# demo_dermis_main_testboard_ncd2400.net
KiCad netlist of a schematic drawn in Altium Designer
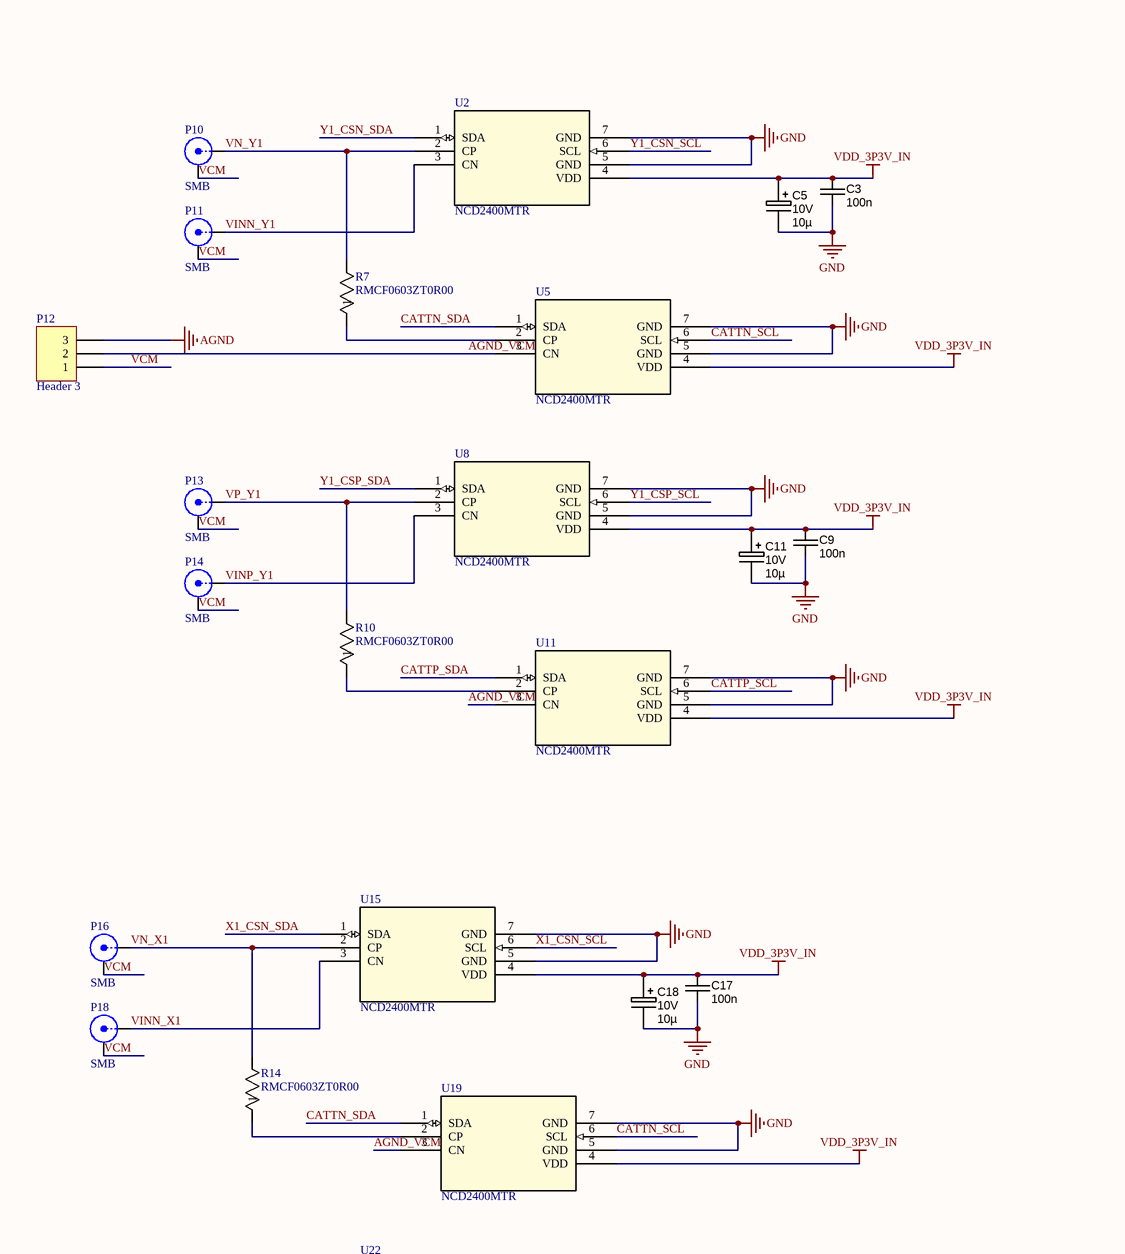
[diagram p0: demo_dermis_main_testboard_ncd2400.SchDoc, top left]
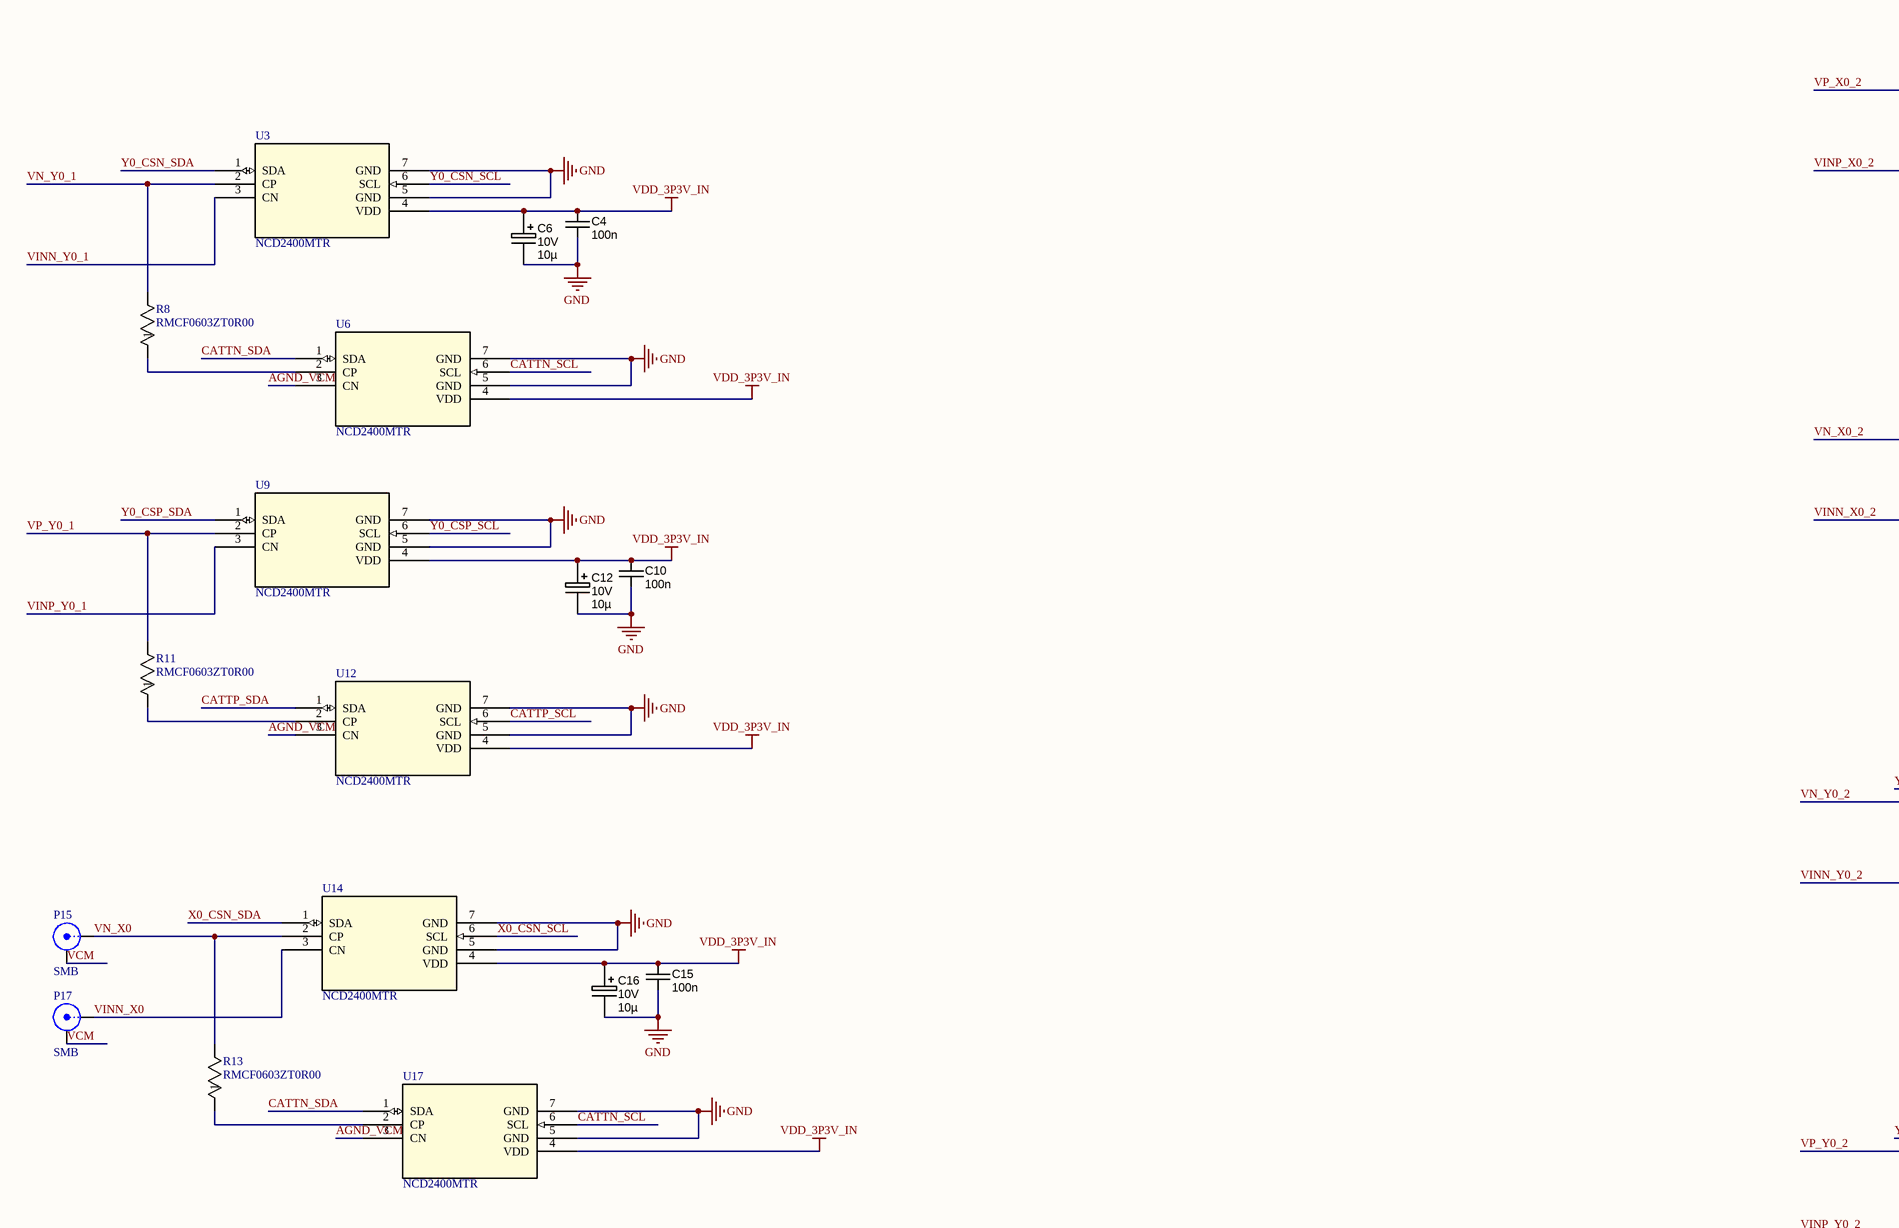
[diagram p1: demo_dermis_main_testboard_ncd2400.SchDoc, top middle]
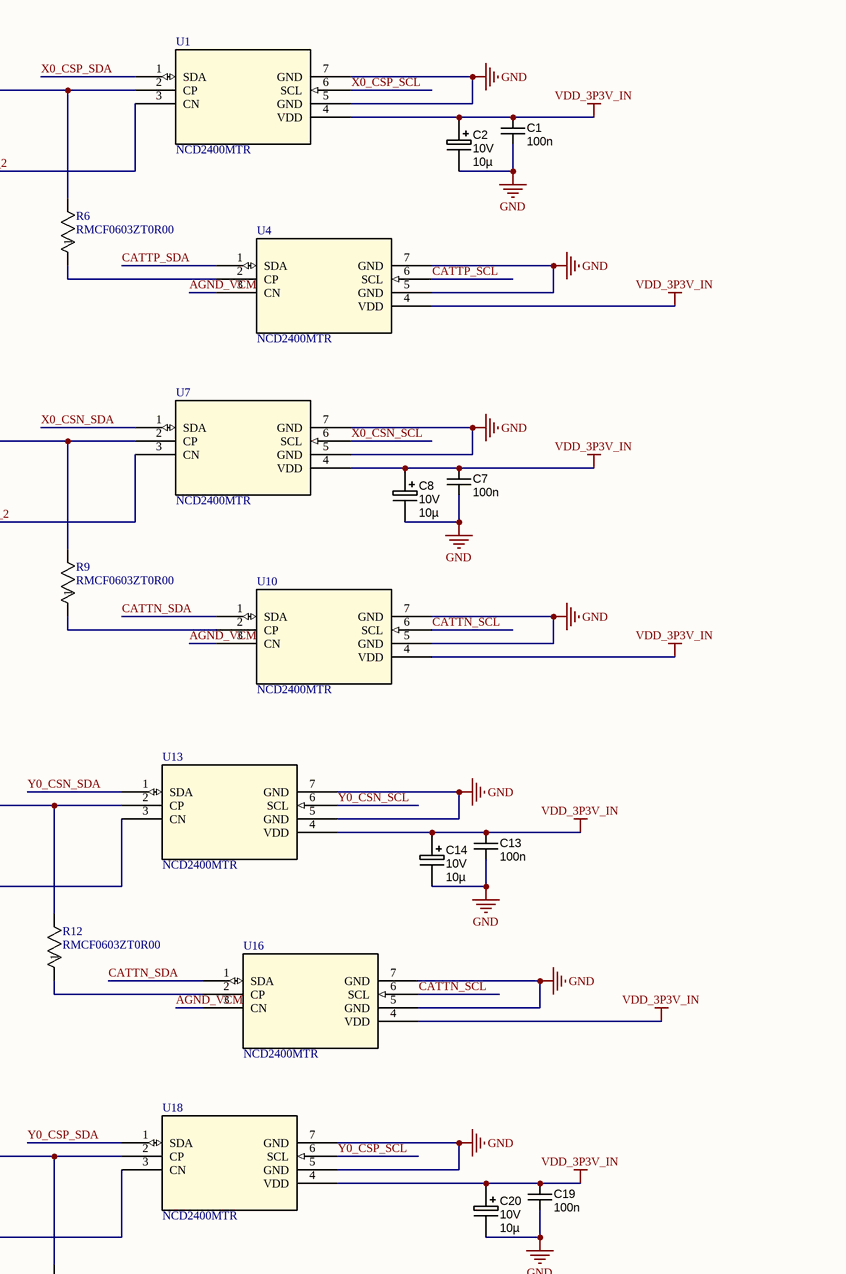
[diagram p2: demo_dermis_main_testboard_ncd2400.SchDoc, top right]
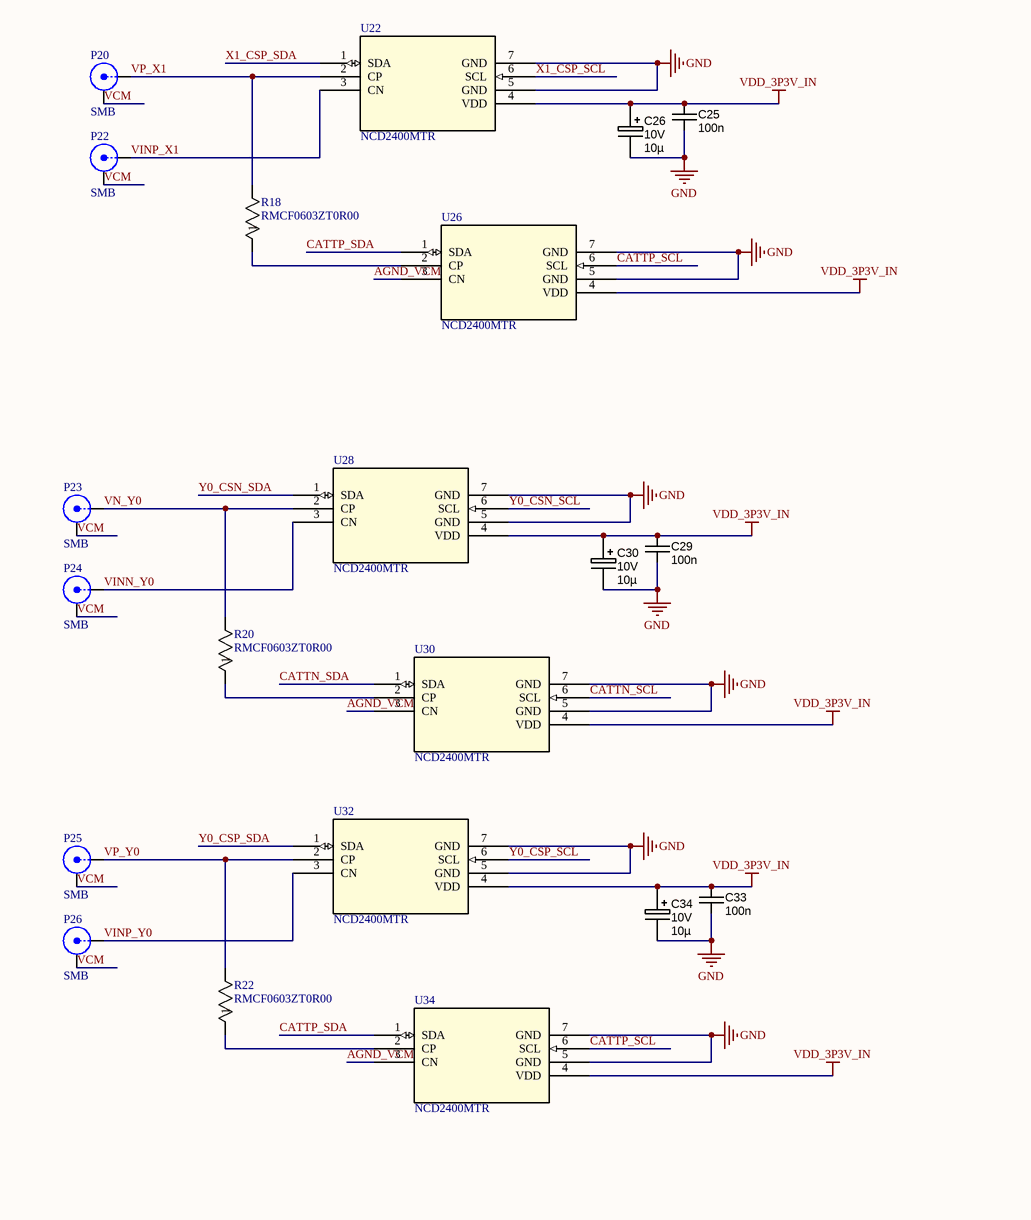
[diagram p3: demo_dermis_main_testboard_ncd2400.SchDoc, bottom left]
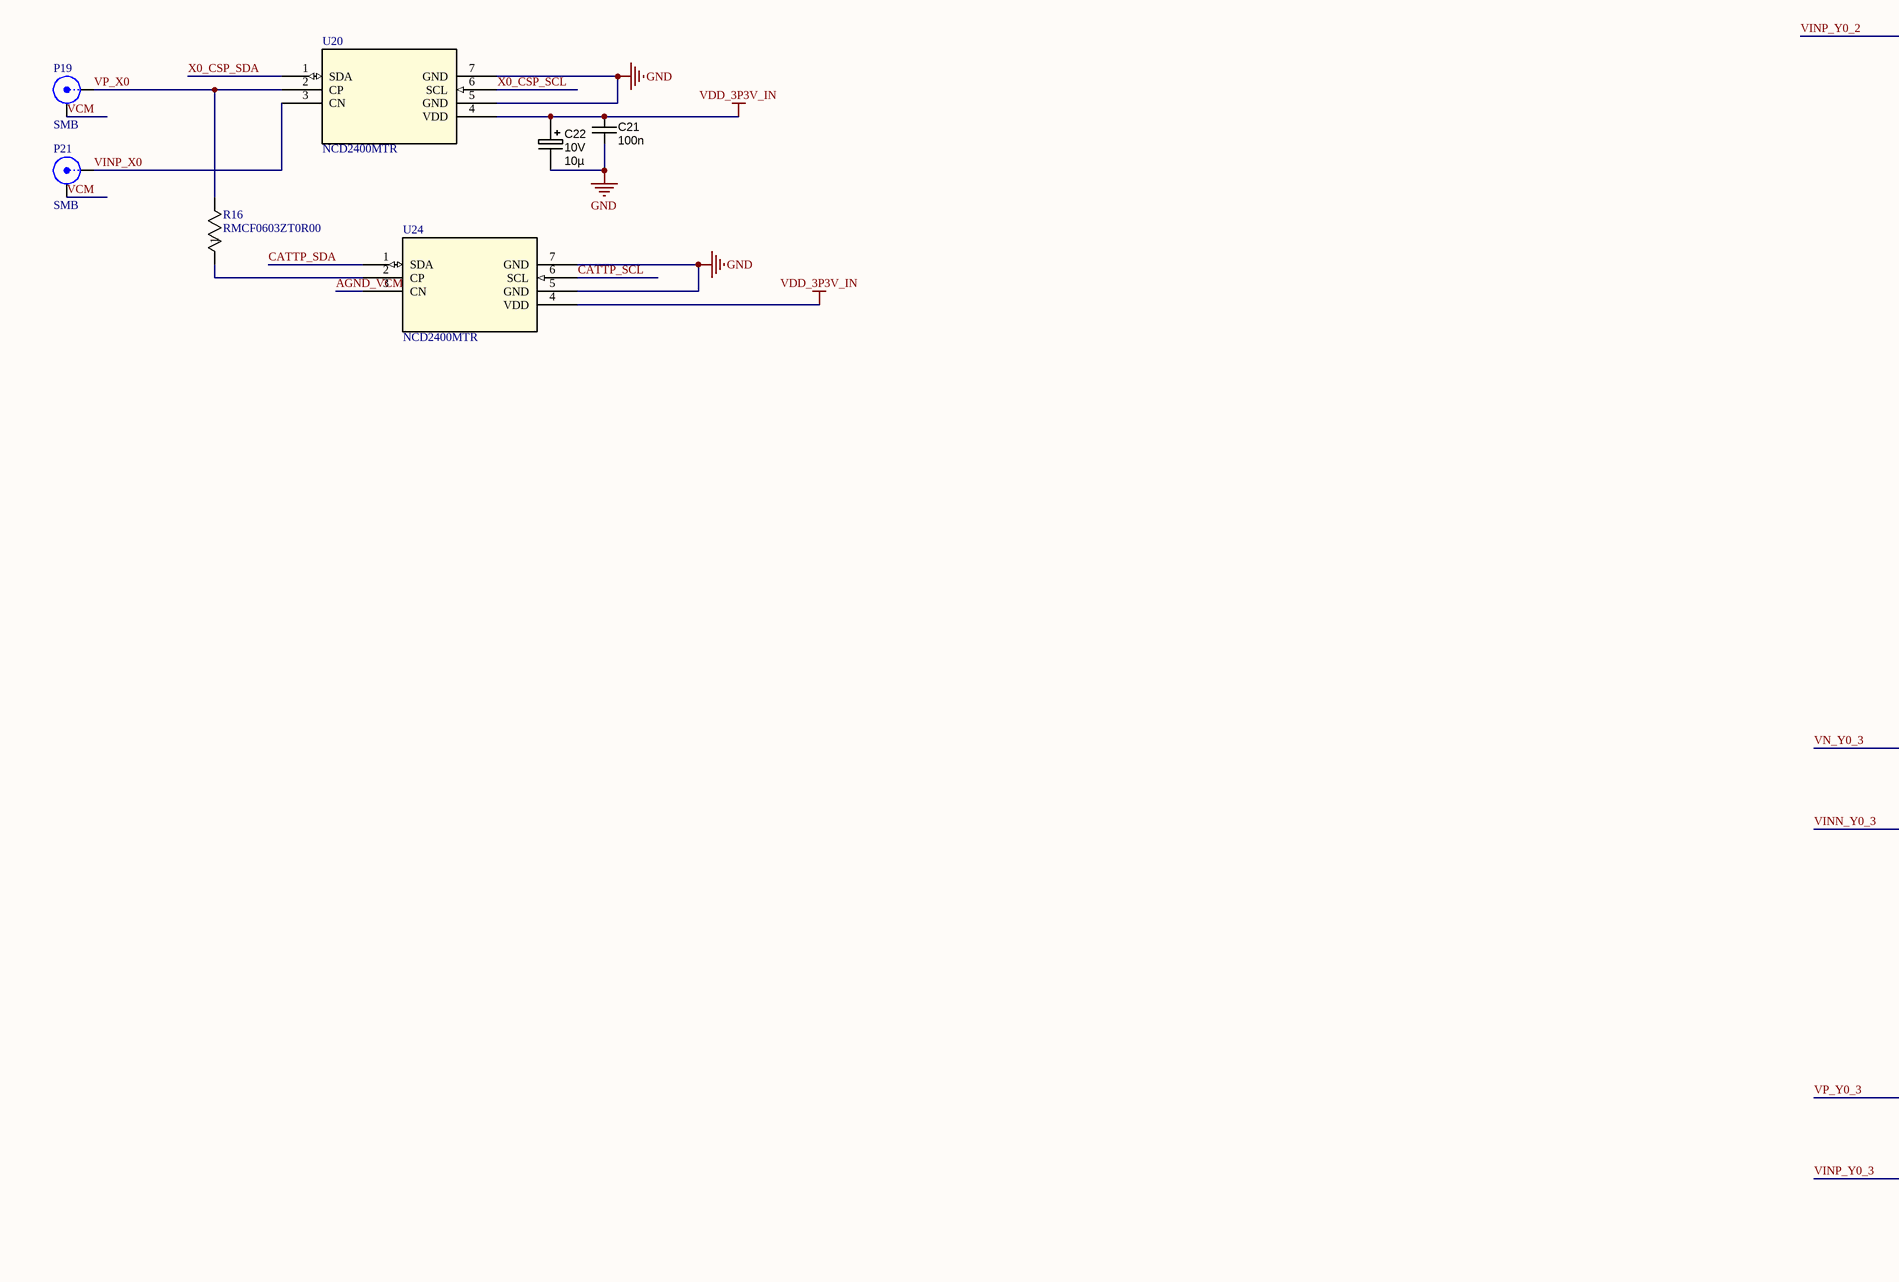
[diagram p4: demo_dermis_main_testboard_ncd2400.SchDoc, bottom middle]
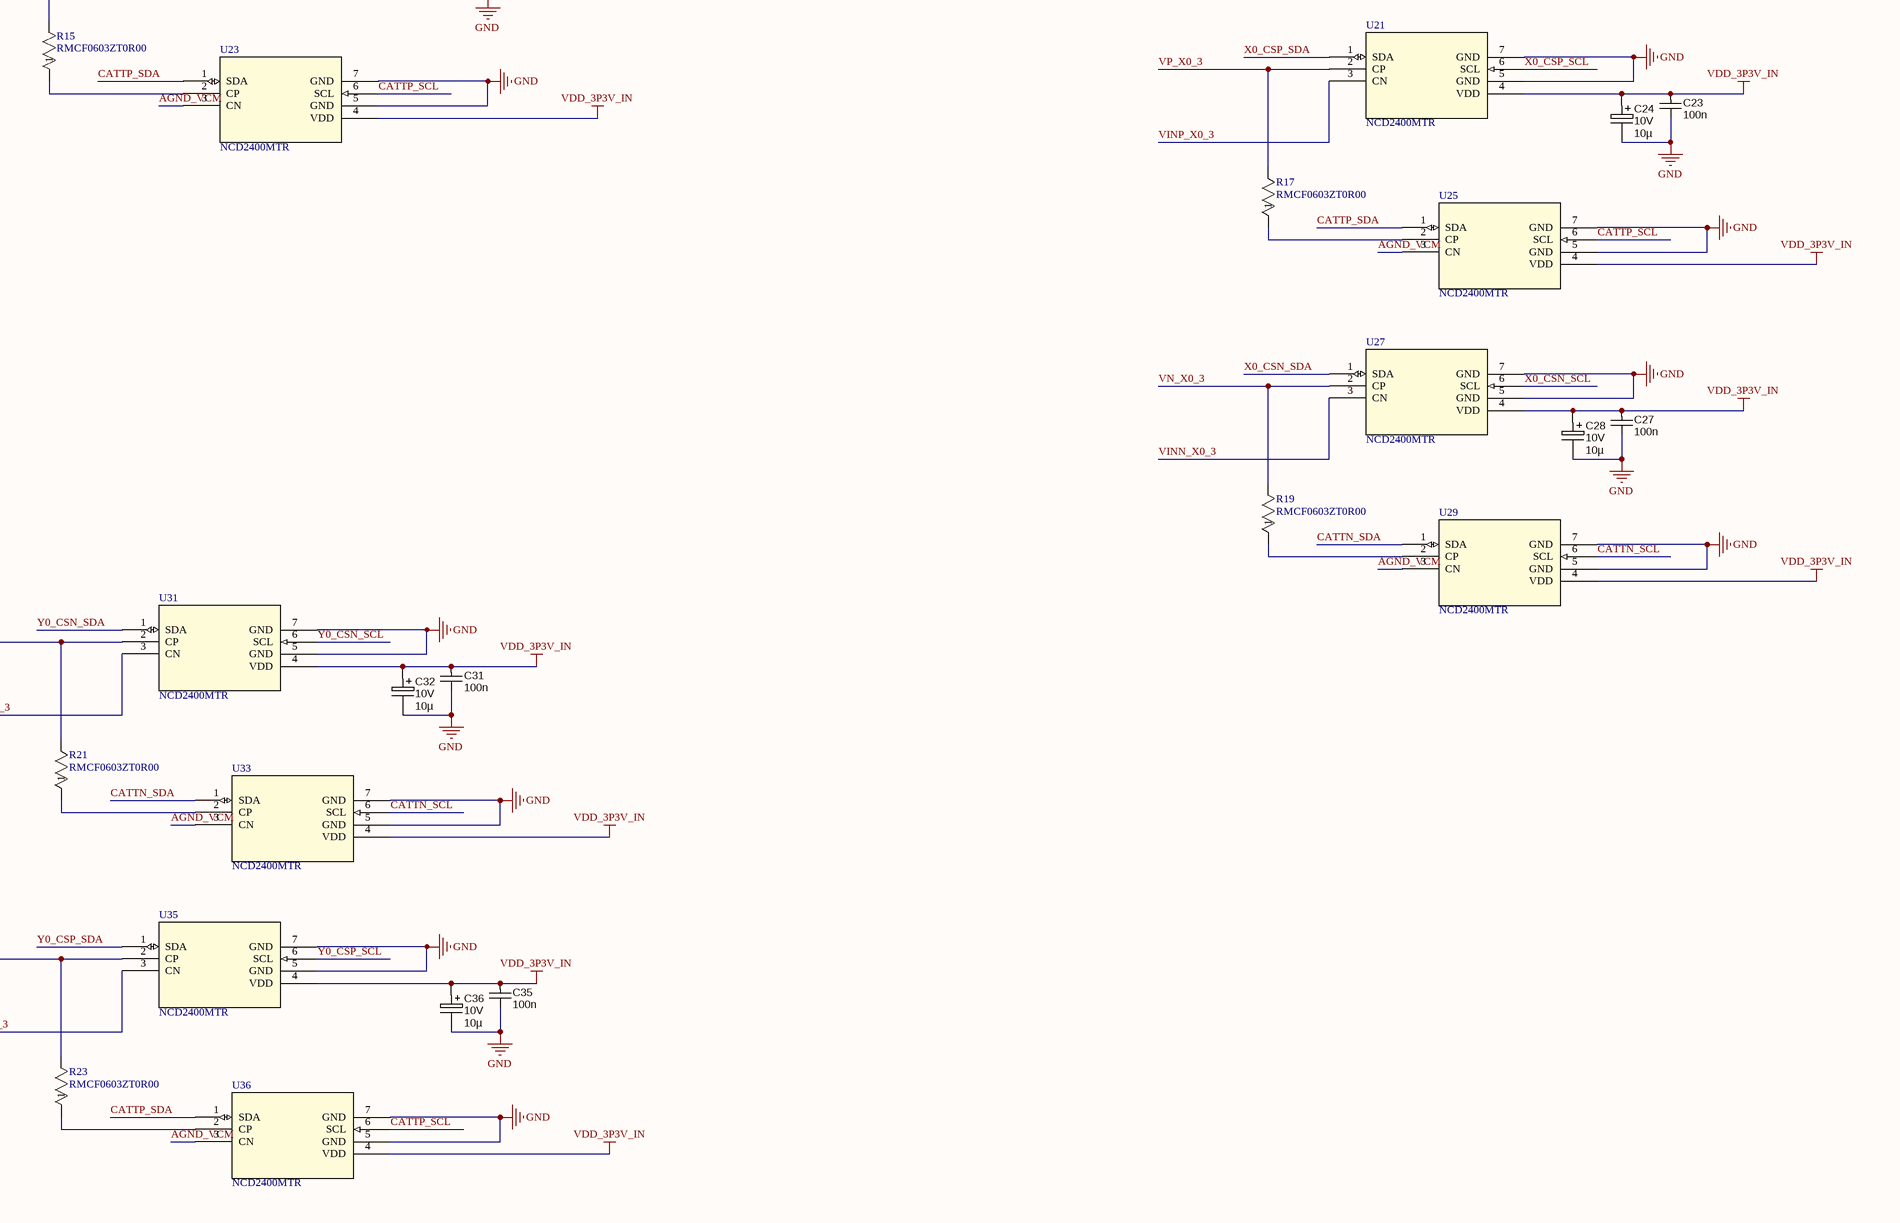
[diagram p5: demo_dermis_main_testboard_ncd2400.SchDoc, bottom right]

(export (version "E")
  (design (tool "Eeschema 10.0.6"))
  (components
    (comp (ref "C1")
      (value "100n")
      (footprint "CAPC1608N")
      (description "Capacitor SMD Cer 100nF 10% 50V X7R 0603")
      (fields (field (name "TOLERANCE") "±10%") (field (name "Comment") "approved sub OK"))
      (libsource (lib "PBL - Capacitors") (part "CAPC_100n_0603"))
    )
    (comp (ref "C2")
      (value "10µ")
      (footprint "CAPMP2012X150USR")
      (description "Capacitor SMD Tantalum 10uF 20% 10V 0805")
      (fields (field (name "TOLERANCE") "±20%") (field (name "RATINGS") "10V"))
      (libsource (lib "PBL - Capacitors") (part "CAPT_10u_0805_10V"))
    )
    (comp (ref "C3")
      (value "100n")
      (footprint "CAPC1608N")
      (description "Capacitor SMD Cer 100nF 10% 50V X7R 0603")
      (fields (field (name "TOLERANCE") "±10%") (field (name "Comment") "approved sub OK"))
      (libsource (lib "PBL - Capacitors") (part "CAPC_100n_0603"))
    )
    (comp (ref "C4")
      (value "100n")
      (footprint "CAPC1608N")
      (description "Capacitor SMD Cer 100nF 10% 50V X7R 0603")
      (fields (field (name "TOLERANCE") "±10%") (field (name "Comment") "approved sub OK"))
      (libsource (lib "PBL - Capacitors") (part "CAPC_100n_0603"))
    )
    (comp (ref "C5")
      (value "10µ")
      (footprint "CAPMP2012X150USR")
      (description "Capacitor SMD Tantalum 10uF 20% 10V 0805")
      (fields (field (name "TOLERANCE") "±20%") (field (name "RATINGS") "10V"))
      (libsource (lib "PBL - Capacitors") (part "CAPT_10u_0805_10V"))
    )
    (comp (ref "C6")
      (value "10µ")
      (footprint "CAPMP2012X150USR")
      (description "Capacitor SMD Tantalum 10uF 20% 10V 0805")
      (fields (field (name "TOLERANCE") "±20%") (field (name "RATINGS") "10V"))
      (libsource (lib "PBL - Capacitors") (part "CAPT_10u_0805_10V"))
    )
    (comp (ref "C7")
      (value "100n")
      (footprint "CAPC1608N")
      (description "Capacitor SMD Cer 100nF 10% 50V X7R 0603")
      (fields (field (name "TOLERANCE") "±10%") (field (name "Comment") "approved sub OK"))
      (libsource (lib "PBL - Capacitors") (part "CAPC_100n_0603"))
    )
    (comp (ref "C8")
      (value "10µ")
      (footprint "CAPMP2012X150USR")
      (description "Capacitor SMD Tantalum 10uF 20% 10V 0805")
      (fields (field (name "TOLERANCE") "±20%") (field (name "RATINGS") "10V"))
      (libsource (lib "PBL - Capacitors") (part "CAPT_10u_0805_10V"))
    )
    (comp (ref "C9")
      (value "100n")
      (footprint "CAPC1608N")
      (description "Capacitor SMD Cer 100nF 10% 50V X7R 0603")
      (fields (field (name "TOLERANCE") "±10%") (field (name "Comment") "approved sub OK"))
      (libsource (lib "PBL - Capacitors") (part "CAPC_100n_0603"))
    )
    (comp (ref "C10")
      (value "100n")
      (footprint "CAPC1608N")
      (description "Capacitor SMD Cer 100nF 10% 50V X7R 0603")
      (fields (field (name "TOLERANCE") "±10%") (field (name "Comment") "approved sub OK"))
      (libsource (lib "PBL - Capacitors") (part "CAPC_100n_0603"))
    )
    (comp (ref "C11")
      (value "10µ")
      (footprint "CAPMP2012X150USR")
      (description "Capacitor SMD Tantalum 10uF 20% 10V 0805")
      (fields (field (name "TOLERANCE") "±20%") (field (name "RATINGS") "10V"))
      (libsource (lib "PBL - Capacitors") (part "CAPT_10u_0805_10V"))
    )
    (comp (ref "C12")
      (value "10µ")
      (footprint "CAPMP2012X150USR")
      (description "Capacitor SMD Tantalum 10uF 20% 10V 0805")
      (fields (field (name "TOLERANCE") "±20%") (field (name "RATINGS") "10V"))
      (libsource (lib "PBL - Capacitors") (part "CAPT_10u_0805_10V"))
    )
    (comp (ref "C13")
      (value "100n")
      (footprint "CAPC1608N")
      (description "Capacitor SMD Cer 100nF 10% 50V X7R 0603")
      (fields (field (name "TOLERANCE") "±10%") (field (name "Comment") "approved sub OK"))
      (libsource (lib "PBL - Capacitors") (part "CAPC_100n_0603"))
    )
    (comp (ref "C14")
      (value "10µ")
      (footprint "CAPMP2012X150USR")
      (description "Capacitor SMD Tantalum 10uF 20% 10V 0805")
      (fields (field (name "TOLERANCE") "±20%") (field (name "RATINGS") "10V"))
      (libsource (lib "PBL - Capacitors") (part "CAPT_10u_0805_10V"))
    )
    (comp (ref "C15")
      (value "100n")
      (footprint "CAPC1608N")
      (description "Capacitor SMD Cer 100nF 10% 50V X7R 0603")
      (fields (field (name "TOLERANCE") "±10%") (field (name "Comment") "approved sub OK"))
      (libsource (lib "PBL - Capacitors") (part "CAPC_100n_0603"))
    )
    (comp (ref "C16")
      (value "10µ")
      (footprint "CAPMP2012X150USR")
      (description "Capacitor SMD Tantalum 10uF 20% 10V 0805")
      (fields (field (name "TOLERANCE") "±20%") (field (name "RATINGS") "10V"))
      (libsource (lib "PBL - Capacitors") (part "CAPT_10u_0805_10V"))
    )
    (comp (ref "C17")
      (value "100n")
      (footprint "CAPC1608N")
      (description "Capacitor SMD Cer 100nF 10% 50V X7R 0603")
      (fields (field (name "TOLERANCE") "±10%") (field (name "Comment") "approved sub OK"))
      (libsource (lib "PBL - Capacitors") (part "CAPC_100n_0603"))
    )
    (comp (ref "C18")
      (value "10µ")
      (footprint "CAPMP2012X150USR")
      (description "Capacitor SMD Tantalum 10uF 20% 10V 0805")
      (fields (field (name "TOLERANCE") "±20%") (field (name "RATINGS") "10V"))
      (libsource (lib "PBL - Capacitors") (part "CAPT_10u_0805_10V"))
    )
    (comp (ref "C19")
      (value "100n")
      (footprint "CAPC1608N")
      (description "Capacitor SMD Cer 100nF 10% 50V X7R 0603")
      (fields (field (name "TOLERANCE") "±10%") (field (name "Comment") "approved sub OK"))
      (libsource (lib "PBL - Capacitors") (part "CAPC_100n_0603"))
    )
    (comp (ref "C20")
      (value "10µ")
      (footprint "CAPMP2012X150USR")
      (description "Capacitor SMD Tantalum 10uF 20% 10V 0805")
      (fields (field (name "TOLERANCE") "±20%") (field (name "RATINGS") "10V"))
      (libsource (lib "PBL - Capacitors") (part "CAPT_10u_0805_10V"))
    )
    (comp (ref "C21")
      (value "100n")
      (footprint "CAPC1608N")
      (description "Capacitor SMD Cer 100nF 10% 50V X7R 0603")
      (fields (field (name "TOLERANCE") "±10%") (field (name "Comment") "approved sub OK"))
      (libsource (lib "PBL - Capacitors") (part "CAPC_100n_0603"))
    )
    (comp (ref "C22")
      (value "10µ")
      (footprint "CAPMP2012X150USR")
      (description "Capacitor SMD Tantalum 10uF 20% 10V 0805")
      (fields (field (name "TOLERANCE") "±20%") (field (name "RATINGS") "10V"))
      (libsource (lib "PBL - Capacitors") (part "CAPT_10u_0805_10V"))
    )
    (comp (ref "C23")
      (value "100n")
      (footprint "CAPC1608N")
      (description "Capacitor SMD Cer 100nF 10% 50V X7R 0603")
      (fields (field (name "TOLERANCE") "±10%") (field (name "Comment") "approved sub OK"))
      (libsource (lib "PBL - Capacitors") (part "CAPC_100n_0603"))
    )
    (comp (ref "C24")
      (value "10µ")
      (footprint "CAPMP2012X150USR")
      (description "Capacitor SMD Tantalum 10uF 20% 10V 0805")
      (fields (field (name "TOLERANCE") "±20%") (field (name "RATINGS") "10V"))
      (libsource (lib "PBL - Capacitors") (part "CAPT_10u_0805_10V"))
    )
    (comp (ref "C25")
      (value "100n")
      (footprint "CAPC1608N")
      (description "Capacitor SMD Cer 100nF 10% 50V X7R 0603")
      (fields (field (name "TOLERANCE") "±10%") (field (name "Comment") "approved sub OK"))
      (libsource (lib "PBL - Capacitors") (part "CAPC_100n_0603"))
    )
    (comp (ref "C26")
      (value "10µ")
      (footprint "CAPMP2012X150USR")
      (description "Capacitor SMD Tantalum 10uF 20% 10V 0805")
      (fields (field (name "TOLERANCE") "±20%") (field (name "RATINGS") "10V"))
      (libsource (lib "PBL - Capacitors") (part "CAPT_10u_0805_10V"))
    )
    (comp (ref "C27")
      (value "100n")
      (footprint "CAPC1608N")
      (description "Capacitor SMD Cer 100nF 10% 50V X7R 0603")
      (fields (field (name "TOLERANCE") "±10%") (field (name "Comment") "approved sub OK"))
      (libsource (lib "PBL - Capacitors") (part "CAPC_100n_0603"))
    )
    (comp (ref "C28")
      (value "10µ")
      (footprint "CAPMP2012X150USR")
      (description "Capacitor SMD Tantalum 10uF 20% 10V 0805")
      (fields (field (name "TOLERANCE") "±20%") (field (name "RATINGS") "10V"))
      (libsource (lib "PBL - Capacitors") (part "CAPT_10u_0805_10V"))
    )
    (comp (ref "C29")
      (value "100n")
      (footprint "CAPC1608N")
      (description "Capacitor SMD Cer 100nF 10% 50V X7R 0603")
      (fields (field (name "TOLERANCE") "±10%") (field (name "Comment") "approved sub OK"))
      (libsource (lib "PBL - Capacitors") (part "CAPC_100n_0603"))
    )
    (comp (ref "C30")
      (value "10µ")
      (footprint "CAPMP2012X150USR")
      (description "Capacitor SMD Tantalum 10uF 20% 10V 0805")
      (fields (field (name "TOLERANCE") "±20%") (field (name "RATINGS") "10V"))
      (libsource (lib "PBL - Capacitors") (part "CAPT_10u_0805_10V"))
    )
    (comp (ref "C31")
      (value "100n")
      (footprint "CAPC1608N")
      (description "Capacitor SMD Cer 100nF 10% 50V X7R 0603")
      (fields (field (name "TOLERANCE") "±10%") (field (name "Comment") "approved sub OK"))
      (libsource (lib "PBL - Capacitors") (part "CAPC_100n_0603"))
    )
    (comp (ref "C32")
      (value "10µ")
      (footprint "CAPMP2012X150USR")
      (description "Capacitor SMD Tantalum 10uF 20% 10V 0805")
      (fields (field (name "TOLERANCE") "±20%") (field (name "RATINGS") "10V"))
      (libsource (lib "PBL - Capacitors") (part "CAPT_10u_0805_10V"))
    )
    (comp (ref "C33")
      (value "100n")
      (footprint "CAPC1608N")
      (description "Capacitor SMD Cer 100nF 10% 50V X7R 0603")
      (fields (field (name "TOLERANCE") "±10%") (field (name "Comment") "approved sub OK"))
      (libsource (lib "PBL - Capacitors") (part "CAPC_100n_0603"))
    )
    (comp (ref "C34")
      (value "10µ")
      (footprint "CAPMP2012X150USR")
      (description "Capacitor SMD Tantalum 10uF 20% 10V 0805")
      (fields (field (name "TOLERANCE") "±20%") (field (name "RATINGS") "10V"))
      (libsource (lib "PBL - Capacitors") (part "CAPT_10u_0805_10V"))
    )
    (comp (ref "C35")
      (value "100n")
      (footprint "CAPC1608N")
      (description "Capacitor SMD Cer 100nF 10% 50V X7R 0603")
      (fields (field (name "TOLERANCE") "±10%") (field (name "Comment") "approved sub OK"))
      (libsource (lib "PBL - Capacitors") (part "CAPC_100n_0603"))
    )
    (comp (ref "C36")
      (value "10µ")
      (footprint "CAPMP2012X150USR")
      (description "Capacitor SMD Tantalum 10uF 20% 10V 0805")
      (fields (field (name "TOLERANCE") "±20%") (field (name "RATINGS") "10V"))
      (libsource (lib "PBL - Capacitors") (part "CAPT_10u_0805_10V"))
    )
    (comp (ref "P10")
      (value "SMB")
      (footprint "SMB_V-RJ45")
      (description "SMB Straight Connector")
      (fields (field (name "PUBLISHER") "Altium Limited"))
      (libsource (lib "Miscellaneous Connectors") (part "SMB"))
    )
    (comp (ref "P11")
      (value "SMB")
      (footprint "SMB_V-RJ45")
      (description "SMB Straight Connector")
      (fields (field (name "PUBLISHER") "Altium Limited"))
      (libsource (lib "Miscellaneous Connectors") (part "SMB"))
    )
    (comp (ref "P12")
      (value "Header 3")
      (footprint "HDR1X3")
      (description "Header, 3-Pin")
      (fields (field (name "PUBLISHER") "Altium Limited"))
      (libsource (lib "Miscellaneous Connectors") (part "Header 3"))
    )
    (comp (ref "P13")
      (value "SMB")
      (footprint "SMB_V-RJ45")
      (description "SMB Straight Connector")
      (fields (field (name "PUBLISHER") "Altium Limited"))
      (libsource (lib "Miscellaneous Connectors") (part "SMB"))
    )
    (comp (ref "P14")
      (value "SMB")
      (footprint "SMB_V-RJ45")
      (description "SMB Straight Connector")
      (fields (field (name "PUBLISHER") "Altium Limited"))
      (libsource (lib "Miscellaneous Connectors") (part "SMB"))
    )
    (comp (ref "P15")
      (value "SMB")
      (footprint "SMB_V-RJ45")
      (description "SMB Straight Connector")
      (fields (field (name "PUBLISHER") "Altium Limited"))
      (libsource (lib "Miscellaneous Connectors") (part "SMB"))
    )
    (comp (ref "P16")
      (value "SMB")
      (footprint "SMB_V-RJ45")
      (description "SMB Straight Connector")
      (fields (field (name "PUBLISHER") "Altium Limited"))
      (libsource (lib "Miscellaneous Connectors") (part "SMB"))
    )
    (comp (ref "P17")
      (value "SMB")
      (footprint "SMB_V-RJ45")
      (description "SMB Straight Connector")
      (fields (field (name "PUBLISHER") "Altium Limited"))
      (libsource (lib "Miscellaneous Connectors") (part "SMB"))
    )
    (comp (ref "P18")
      (value "SMB")
      (footprint "SMB_V-RJ45")
      (description "SMB Straight Connector")
      (fields (field (name "PUBLISHER") "Altium Limited"))
      (libsource (lib "Miscellaneous Connectors") (part "SMB"))
    )
    (comp (ref "P19")
      (value "SMB")
      (footprint "SMB_V-RJ45")
      (description "SMB Straight Connector")
      (fields (field (name "PUBLISHER") "Altium Limited"))
      (libsource (lib "Miscellaneous Connectors") (part "SMB"))
    )
    (comp (ref "P20")
      (value "SMB")
      (footprint "SMB_V-RJ45")
      (description "SMB Straight Connector")
      (fields (field (name "PUBLISHER") "Altium Limited"))
      (libsource (lib "Miscellaneous Connectors") (part "SMB"))
    )
    (comp (ref "P21")
      (value "SMB")
      (footprint "SMB_V-RJ45")
      (description "SMB Straight Connector")
      (fields (field (name "PUBLISHER") "Altium Limited"))
      (libsource (lib "Miscellaneous Connectors") (part "SMB"))
    )
    (comp (ref "P22")
      (value "SMB")
      (footprint "SMB_V-RJ45")
      (description "SMB Straight Connector")
      (fields (field (name "PUBLISHER") "Altium Limited"))
      (libsource (lib "Miscellaneous Connectors") (part "SMB"))
    )
    (comp (ref "P23")
      (value "SMB")
      (footprint "SMB_V-RJ45")
      (description "SMB Straight Connector")
      (fields (field (name "PUBLISHER") "Altium Limited"))
      (libsource (lib "Miscellaneous Connectors") (part "SMB"))
    )
    (comp (ref "P24")
      (value "SMB")
      (footprint "SMB_V-RJ45")
      (description "SMB Straight Connector")
      (fields (field (name "PUBLISHER") "Altium Limited"))
      (libsource (lib "Miscellaneous Connectors") (part "SMB"))
    )
    (comp (ref "P25")
      (value "SMB")
      (footprint "SMB_V-RJ45")
      (description "SMB Straight Connector")
      (fields (field (name "PUBLISHER") "Altium Limited"))
      (libsource (lib "Miscellaneous Connectors") (part "SMB"))
    )
    (comp (ref "P26")
      (value "SMB")
      (footprint "SMB_V-RJ45")
      (description "SMB Straight Connector")
      (fields (field (name "PUBLISHER") "Altium Limited"))
      (libsource (lib "Miscellaneous Connectors") (part "SMB"))
    )
    (comp (ref "R6")
      (value "RMCF0603ZT0R00")
      (footprint "STA_RMCF0603_STP")
      (description "No Description Available")
      (libsource (lib "RMCF0603ZT0R00") (part "RMCF0603ZT0R00"))
    )
    (comp (ref "R7")
      (value "RMCF0603ZT0R00")
      (footprint "STA_RMCF0603_STP")
      (description "No Description Available")
      (libsource (lib "RMCF0603ZT0R00") (part "RMCF0603ZT0R00"))
    )
    (comp (ref "R8")
      (value "RMCF0603ZT0R00")
      (footprint "STA_RMCF0603_STP")
      (description "No Description Available")
      (libsource (lib "RMCF0603ZT0R00") (part "RMCF0603ZT0R00"))
    )
    (comp (ref "R9")
      (value "RMCF0603ZT0R00")
      (footprint "STA_RMCF0603_STP")
      (description "No Description Available")
      (libsource (lib "RMCF0603ZT0R00") (part "RMCF0603ZT0R00"))
    )
    (comp (ref "R10")
      (value "RMCF0603ZT0R00")
      (footprint "STA_RMCF0603_STP")
      (description "No Description Available")
      (libsource (lib "RMCF0603ZT0R00") (part "RMCF0603ZT0R00"))
    )
    (comp (ref "R11")
      (value "RMCF0603ZT0R00")
      (footprint "STA_RMCF0603_STP")
      (description "No Description Available")
      (libsource (lib "RMCF0603ZT0R00") (part "RMCF0603ZT0R00"))
    )
    (comp (ref "R12")
      (value "RMCF0603ZT0R00")
      (footprint "STA_RMCF0603_STP")
      (description "No Description Available")
      (libsource (lib "RMCF0603ZT0R00") (part "RMCF0603ZT0R00"))
    )
    (comp (ref "R13")
      (value "RMCF0603ZT0R00")
      (footprint "STA_RMCF0603_STP")
      (description "No Description Available")
      (libsource (lib "RMCF0603ZT0R00") (part "RMCF0603ZT0R00"))
    )
    (comp (ref "R14")
      (value "RMCF0603ZT0R00")
      (footprint "STA_RMCF0603_STP")
      (description "No Description Available")
      (libsource (lib "RMCF0603ZT0R00") (part "RMCF0603ZT0R00"))
    )
    (comp (ref "R15")
      (value "RMCF0603ZT0R00")
      (footprint "STA_RMCF0603_STP")
      (description "No Description Available")
      (libsource (lib "RMCF0603ZT0R00") (part "RMCF0603ZT0R00"))
    )
    (comp (ref "R16")
      (value "RMCF0603ZT0R00")
      (footprint "STA_RMCF0603_STP")
      (description "No Description Available")
      (libsource (lib "RMCF0603ZT0R00") (part "RMCF0603ZT0R00"))
    )
    (comp (ref "R17")
      (value "RMCF0603ZT0R00")
      (footprint "STA_RMCF0603_STP")
      (description "No Description Available")
      (libsource (lib "RMCF0603ZT0R00") (part "RMCF0603ZT0R00"))
    )
    (comp (ref "R18")
      (value "RMCF0603ZT0R00")
      (footprint "STA_RMCF0603_STP")
      (description "No Description Available")
      (libsource (lib "RMCF0603ZT0R00") (part "RMCF0603ZT0R00"))
    )
    (comp (ref "R19")
      (value "RMCF0603ZT0R00")
      (footprint "STA_RMCF0603_STP")
      (description "No Description Available")
      (libsource (lib "RMCF0603ZT0R00") (part "RMCF0603ZT0R00"))
    )
    (comp (ref "R20")
      (value "RMCF0603ZT0R00")
      (footprint "STA_RMCF0603_STP")
      (description "No Description Available")
      (libsource (lib "RMCF0603ZT0R00") (part "RMCF0603ZT0R00"))
    )
    (comp (ref "R21")
      (value "RMCF0603ZT0R00")
      (footprint "STA_RMCF0603_STP")
      (description "No Description Available")
      (libsource (lib "RMCF0603ZT0R00") (part "RMCF0603ZT0R00"))
    )
    (comp (ref "R22")
      (value "RMCF0603ZT0R00")
      (footprint "STA_RMCF0603_STP")
      (description "No Description Available")
      (libsource (lib "RMCF0603ZT0R00") (part "RMCF0603ZT0R00"))
    )
    (comp (ref "R23")
      (value "RMCF0603ZT0R00")
      (footprint "STA_RMCF0603_STP")
      (description "No Description Available")
      (libsource (lib "RMCF0603ZT0R00") (part "RMCF0603ZT0R00"))
    )
    (comp (ref "U1")
      (value "NCD2400MTR")
      (footprint "DFN-6_IXY")
      (description "No Description Available")
      (libsource (lib "NCD2400MTR") (part "NCD2400MTR"))
    )
    (comp (ref "U2")
      (value "NCD2400MTR")
      (footprint "DFN-6_IXY")
      (description "No Description Available")
      (libsource (lib "NCD2400MTR") (part "NCD2400MTR"))
    )
    (comp (ref "U3")
      (value "NCD2400MTR")
      (footprint "DFN-6_IXY")
      (description "No Description Available")
      (libsource (lib "NCD2400MTR") (part "NCD2400MTR"))
    )
    (comp (ref "U4")
      (value "NCD2400MTR")
      (footprint "DFN-6_IXY")
      (description "No Description Available")
      (libsource (lib "NCD2400MTR") (part "NCD2400MTR"))
    )
    (comp (ref "U5")
      (value "NCD2400MTR")
      (footprint "DFN-6_IXY")
      (description "No Description Available")
      (libsource (lib "NCD2400MTR") (part "NCD2400MTR"))
    )
    (comp (ref "U6")
      (value "NCD2400MTR")
      (footprint "DFN-6_IXY")
      (description "No Description Available")
      (libsource (lib "NCD2400MTR") (part "NCD2400MTR"))
    )
    (comp (ref "U7")
      (value "NCD2400MTR")
      (footprint "DFN-6_IXY")
      (description "No Description Available")
      (libsource (lib "NCD2400MTR") (part "NCD2400MTR"))
    )
    (comp (ref "U8")
      (value "NCD2400MTR")
      (footprint "DFN-6_IXY")
      (description "No Description Available")
      (libsource (lib "NCD2400MTR") (part "NCD2400MTR"))
    )
    (comp (ref "U9")
      (value "NCD2400MTR")
      (footprint "DFN-6_IXY")
      (description "No Description Available")
      (libsource (lib "NCD2400MTR") (part "NCD2400MTR"))
    )
    (comp (ref "U10")
      (value "NCD2400MTR")
      (footprint "DFN-6_IXY")
      (description "No Description Available")
      (libsource (lib "NCD2400MTR") (part "NCD2400MTR"))
    )
    (comp (ref "U11")
      (value "NCD2400MTR")
      (footprint "DFN-6_IXY")
      (description "No Description Available")
      (libsource (lib "NCD2400MTR") (part "NCD2400MTR"))
    )
    (comp (ref "U12")
      (value "NCD2400MTR")
      (footprint "DFN-6_IXY")
      (description "No Description Available")
      (libsource (lib "NCD2400MTR") (part "NCD2400MTR"))
    )
    (comp (ref "U13")
      (value "NCD2400MTR")
      (footprint "DFN-6_IXY")
      (description "No Description Available")
      (libsource (lib "NCD2400MTR") (part "NCD2400MTR"))
    )
    (comp (ref "U14")
      (value "NCD2400MTR")
      (footprint "DFN-6_IXY")
      (description "No Description Available")
      (libsource (lib "NCD2400MTR") (part "NCD2400MTR"))
    )
    (comp (ref "U15")
      (value "NCD2400MTR")
      (footprint "DFN-6_IXY")
      (description "No Description Available")
      (libsource (lib "NCD2400MTR") (part "NCD2400MTR"))
    )
    (comp (ref "U16")
      (value "NCD2400MTR")
      (footprint "DFN-6_IXY")
      (description "No Description Available")
      (libsource (lib "NCD2400MTR") (part "NCD2400MTR"))
    )
    (comp (ref "U17")
      (value "NCD2400MTR")
      (footprint "DFN-6_IXY")
      (description "No Description Available")
      (libsource (lib "NCD2400MTR") (part "NCD2400MTR"))
    )
    (comp (ref "U18")
      (value "NCD2400MTR")
      (footprint "DFN-6_IXY")
      (description "No Description Available")
      (libsource (lib "NCD2400MTR") (part "NCD2400MTR"))
    )
    (comp (ref "U19")
      (value "NCD2400MTR")
      (footprint "DFN-6_IXY")
      (description "No Description Available")
      (libsource (lib "NCD2400MTR") (part "NCD2400MTR"))
    )
    (comp (ref "U20")
      (value "NCD2400MTR")
      (footprint "DFN-6_IXY")
      (description "No Description Available")
      (libsource (lib "NCD2400MTR") (part "NCD2400MTR"))
    )
    (comp (ref "U21")
      (value "NCD2400MTR")
      (footprint "DFN-6_IXY")
      (description "No Description Available")
      (libsource (lib "NCD2400MTR") (part "NCD2400MTR"))
    )
    (comp (ref "U22")
      (value "NCD2400MTR")
      (footprint "DFN-6_IXY")
      (description "No Description Available")
      (libsource (lib "NCD2400MTR") (part "NCD2400MTR"))
    )
    (comp (ref "U23")
      (value "NCD2400MTR")
      (footprint "DFN-6_IXY")
      (description "No Description Available")
      (libsource (lib "NCD2400MTR") (part "NCD2400MTR"))
    )
    (comp (ref "U24")
      (value "NCD2400MTR")
      (footprint "DFN-6_IXY")
      (description "No Description Available")
      (libsource (lib "NCD2400MTR") (part "NCD2400MTR"))
    )
    (comp (ref "U25")
      (value "NCD2400MTR")
      (footprint "DFN-6_IXY")
      (description "No Description Available")
      (libsource (lib "NCD2400MTR") (part "NCD2400MTR"))
    )
    (comp (ref "U26")
      (value "NCD2400MTR")
      (footprint "DFN-6_IXY")
      (description "No Description Available")
      (libsource (lib "NCD2400MTR") (part "NCD2400MTR"))
    )
    (comp (ref "U27")
      (value "NCD2400MTR")
      (footprint "DFN-6_IXY")
      (description "No Description Available")
      (libsource (lib "NCD2400MTR") (part "NCD2400MTR"))
    )
    (comp (ref "U28")
      (value "NCD2400MTR")
      (footprint "DFN-6_IXY")
      (description "No Description Available")
      (libsource (lib "NCD2400MTR") (part "NCD2400MTR"))
    )
    (comp (ref "U29")
      (value "NCD2400MTR")
      (footprint "DFN-6_IXY")
      (description "No Description Available")
      (libsource (lib "NCD2400MTR") (part "NCD2400MTR"))
    )
    (comp (ref "U30")
      (value "NCD2400MTR")
      (footprint "DFN-6_IXY")
      (description "No Description Available")
      (libsource (lib "NCD2400MTR") (part "NCD2400MTR"))
    )
    (comp (ref "U31")
      (value "NCD2400MTR")
      (footprint "DFN-6_IXY")
      (description "No Description Available")
      (libsource (lib "NCD2400MTR") (part "NCD2400MTR"))
    )
    (comp (ref "U32")
      (value "NCD2400MTR")
      (footprint "DFN-6_IXY")
      (description "No Description Available")
      (libsource (lib "NCD2400MTR") (part "NCD2400MTR"))
    )
    (comp (ref "U33")
      (value "NCD2400MTR")
      (footprint "DFN-6_IXY")
      (description "No Description Available")
      (libsource (lib "NCD2400MTR") (part "NCD2400MTR"))
    )
    (comp (ref "U34")
      (value "NCD2400MTR")
      (footprint "DFN-6_IXY")
      (description "No Description Available")
      (libsource (lib "NCD2400MTR") (part "NCD2400MTR"))
    )
    (comp (ref "U35")
      (value "NCD2400MTR")
      (footprint "DFN-6_IXY")
      (description "No Description Available")
      (libsource (lib "NCD2400MTR") (part "NCD2400MTR"))
    )
    (comp (ref "U36")
      (value "NCD2400MTR")
      (footprint "DFN-6_IXY")
      (description "No Description Available")
      (libsource (lib "NCD2400MTR") (part "NCD2400MTR"))
    )
  )
  (nets
    (net (code "1") (name "/AGND_VCM") (class "Default")
      (node (ref "P12") (pin "2") (pinfunction "2_2") (pintype "passive"))
      (node (ref "U10") (pin "3") (pinfunction "CN_3") (pintype "power_in"))
      (node (ref "U11") (pin "3") (pinfunction "CN_3") (pintype "power_in"))
      (node (ref "U12") (pin "3") (pinfunction "CN_3") (pintype "power_in"))
      (node (ref "U16") (pin "3") (pinfunction "CN_3") (pintype "power_in"))
      (node (ref "U17") (pin "3") (pinfunction "CN_3") (pintype "power_in"))
      (node (ref "U19") (pin "3") (pinfunction "CN_3") (pintype "power_in"))
      (node (ref "U23") (pin "3") (pinfunction "CN_3") (pintype "power_in"))
      (node (ref "U24") (pin "3") (pinfunction "CN_3") (pintype "power_in"))
      (node (ref "U25") (pin "3") (pinfunction "CN_3") (pintype "power_in"))
      (node (ref "U26") (pin "3") (pinfunction "CN_3") (pintype "power_in"))
      (node (ref "U29") (pin "3") (pinfunction "CN_3") (pintype "power_in"))
      (node (ref "U30") (pin "3") (pinfunction "CN_3") (pintype "power_in"))
      (node (ref "U33") (pin "3") (pinfunction "CN_3") (pintype "power_in"))
      (node (ref "U34") (pin "3") (pinfunction "CN_3") (pintype "power_in"))
      (node (ref "U36") (pin "3") (pinfunction "CN_3") (pintype "power_in"))
      (node (ref "U4") (pin "3") (pinfunction "CN_3") (pintype "power_in"))
      (node (ref "U5") (pin "3") (pinfunction "CN_3") (pintype "power_in"))
      (node (ref "U6") (pin "3") (pinfunction "CN_3") (pintype "power_in"))
    )
    (net (code "2") (name "/CATTN_SCL") (class "Default")
      (node (ref "U10") (pin "6") (pinfunction "SCL_6") (pintype "input"))
      (node (ref "U16") (pin "6") (pinfunction "SCL_6") (pintype "input"))
      (node (ref "U17") (pin "6") (pinfunction "SCL_6") (pintype "input"))
      (node (ref "U19") (pin "6") (pinfunction "SCL_6") (pintype "input"))
      (node (ref "U29") (pin "6") (pinfunction "SCL_6") (pintype "input"))
      (node (ref "U30") (pin "6") (pinfunction "SCL_6") (pintype "input"))
      (node (ref "U33") (pin "6") (pinfunction "SCL_6") (pintype "input"))
      (node (ref "U5") (pin "6") (pinfunction "SCL_6") (pintype "input"))
      (node (ref "U6") (pin "6") (pinfunction "SCL_6") (pintype "input"))
    )
    (net (code "3") (name "/CATTN_SDA") (class "Default")
      (node (ref "U10") (pin "1") (pinfunction "SDA_1") (pintype "bidirectional"))
      (node (ref "U16") (pin "1") (pinfunction "SDA_1") (pintype "bidirectional"))
      (node (ref "U17") (pin "1") (pinfunction "SDA_1") (pintype "bidirectional"))
      (node (ref "U19") (pin "1") (pinfunction "SDA_1") (pintype "bidirectional"))
      (node (ref "U29") (pin "1") (pinfunction "SDA_1") (pintype "bidirectional"))
      (node (ref "U30") (pin "1") (pinfunction "SDA_1") (pintype "bidirectional"))
      (node (ref "U33") (pin "1") (pinfunction "SDA_1") (pintype "bidirectional"))
      (node (ref "U5") (pin "1") (pinfunction "SDA_1") (pintype "bidirectional"))
      (node (ref "U6") (pin "1") (pinfunction "SDA_1") (pintype "bidirectional"))
    )
    (net (code "4") (name "/CATTP_SCL") (class "Default")
      (node (ref "U11") (pin "6") (pinfunction "SCL_6") (pintype "input"))
      (node (ref "U12") (pin "6") (pinfunction "SCL_6") (pintype "input"))
      (node (ref "U23") (pin "6") (pinfunction "SCL_6") (pintype "input"))
      (node (ref "U24") (pin "6") (pinfunction "SCL_6") (pintype "input"))
      (node (ref "U25") (pin "6") (pinfunction "SCL_6") (pintype "input"))
      (node (ref "U26") (pin "6") (pinfunction "SCL_6") (pintype "input"))
      (node (ref "U34") (pin "6") (pinfunction "SCL_6") (pintype "input"))
      (node (ref "U36") (pin "6") (pinfunction "SCL_6") (pintype "input"))
      (node (ref "U4") (pin "6") (pinfunction "SCL_6") (pintype "input"))
    )
    (net (code "5") (name "/CATTP_SDA") (class "Default")
      (node (ref "U11") (pin "1") (pinfunction "SDA_1") (pintype "bidirectional"))
      (node (ref "U12") (pin "1") (pinfunction "SDA_1") (pintype "bidirectional"))
      (node (ref "U23") (pin "1") (pinfunction "SDA_1") (pintype "bidirectional"))
      (node (ref "U24") (pin "1") (pinfunction "SDA_1") (pintype "bidirectional"))
      (node (ref "U25") (pin "1") (pinfunction "SDA_1") (pintype "bidirectional"))
      (node (ref "U26") (pin "1") (pinfunction "SDA_1") (pintype "bidirectional"))
      (node (ref "U34") (pin "1") (pinfunction "SDA_1") (pintype "bidirectional"))
      (node (ref "U36") (pin "1") (pinfunction "SDA_1") (pintype "bidirectional"))
      (node (ref "U4") (pin "1") (pinfunction "SDA_1") (pintype "bidirectional"))
    )
    (net (code "6") (name "/VCM") (class "Default")
      (node (ref "P10") (pin "2") (pinfunction "Y_2") (pintype "passive"))
      (node (ref "P11") (pin "2") (pinfunction "Y_2") (pintype "passive"))
      (node (ref "P12") (pin "1") (pinfunction "1_1") (pintype "passive"))
      (node (ref "P13") (pin "2") (pinfunction "Y_2") (pintype "passive"))
      (node (ref "P14") (pin "2") (pinfunction "Y_2") (pintype "passive"))
      (node (ref "P15") (pin "2") (pinfunction "Y_2") (pintype "passive"))
      (node (ref "P16") (pin "2") (pinfunction "Y_2") (pintype "passive"))
      (node (ref "P17") (pin "2") (pinfunction "Y_2") (pintype "passive"))
      (node (ref "P18") (pin "2") (pinfunction "Y_2") (pintype "passive"))
      (node (ref "P19") (pin "2") (pinfunction "Y_2") (pintype "passive"))
      (node (ref "P20") (pin "2") (pinfunction "Y_2") (pintype "passive"))
      (node (ref "P21") (pin "2") (pinfunction "Y_2") (pintype "passive"))
      (node (ref "P22") (pin "2") (pinfunction "Y_2") (pintype "passive"))
      (node (ref "P23") (pin "2") (pinfunction "Y_2") (pintype "passive"))
      (node (ref "P24") (pin "2") (pinfunction "Y_2") (pintype "passive"))
      (node (ref "P25") (pin "2") (pinfunction "Y_2") (pintype "passive"))
      (node (ref "P26") (pin "2") (pinfunction "Y_2") (pintype "passive"))
    )
    (net (code "7") (name "/VINN_X0") (class "Default")
      (node (ref "P17") (pin "1") (pinfunction "X_1") (pintype "passive"))
      (node (ref "U14") (pin "3") (pinfunction "CN_3") (pintype "power_in"))
    )
    (net (code "8") (name "/VINN_X0_2") (class "Default")
      (node (ref "U7") (pin "3") (pinfunction "CN_3") (pintype "power_in"))
    )
    (net (code "9") (name "/VINN_X0_3") (class "Default")
      (node (ref "U27") (pin "3") (pinfunction "CN_3") (pintype "power_in"))
    )
    (net (code "10") (name "/VINN_X1") (class "Default")
      (node (ref "P18") (pin "1") (pinfunction "X_1") (pintype "passive"))
      (node (ref "U15") (pin "3") (pinfunction "CN_3") (pintype "power_in"))
    )
    (net (code "11") (name "/VINN_Y0") (class "Default")
      (node (ref "P24") (pin "1") (pinfunction "X_1") (pintype "passive"))
      (node (ref "U28") (pin "3") (pinfunction "CN_3") (pintype "power_in"))
    )
    (net (code "12") (name "/VINN_Y0_1") (class "Default")
      (node (ref "U3") (pin "3") (pinfunction "CN_3") (pintype "power_in"))
    )
    (net (code "13") (name "/VINN_Y0_2") (class "Default")
      (node (ref "U13") (pin "3") (pinfunction "CN_3") (pintype "power_in"))
    )
    (net (code "14") (name "/VINN_Y0_3") (class "Default")
      (node (ref "U31") (pin "3") (pinfunction "CN_3") (pintype "power_in"))
    )
    (net (code "15") (name "/VINN_Y1") (class "Default")
      (node (ref "P11") (pin "1") (pinfunction "X_1") (pintype "passive"))
      (node (ref "U2") (pin "3") (pinfunction "CN_3") (pintype "power_in"))
    )
    (net (code "16") (name "/VINP_X0") (class "Default")
      (node (ref "P21") (pin "1") (pinfunction "X_1") (pintype "passive"))
      (node (ref "U20") (pin "3") (pinfunction "CN_3") (pintype "power_in"))
    )
    (net (code "17") (name "/VINP_X0_2") (class "Default")
      (node (ref "U1") (pin "3") (pinfunction "CN_3") (pintype "power_in"))
    )
    (net (code "18") (name "/VINP_X0_3") (class "Default")
      (node (ref "U21") (pin "3") (pinfunction "CN_3") (pintype "power_in"))
    )
    (net (code "19") (name "/VINP_X1") (class "Default")
      (node (ref "P22") (pin "1") (pinfunction "X_1") (pintype "passive"))
      (node (ref "U22") (pin "3") (pinfunction "CN_3") (pintype "power_in"))
    )
    (net (code "20") (name "/VINP_Y0") (class "Default")
      (node (ref "P26") (pin "1") (pinfunction "X_1") (pintype "passive"))
      (node (ref "U32") (pin "3") (pinfunction "CN_3") (pintype "power_in"))
    )
    (net (code "21") (name "/VINP_Y0_1") (class "Default")
      (node (ref "U9") (pin "3") (pinfunction "CN_3") (pintype "power_in"))
    )
    (net (code "22") (name "/VINP_Y0_2") (class "Default")
      (node (ref "U18") (pin "3") (pinfunction "CN_3") (pintype "power_in"))
    )
    (net (code "23") (name "/VINP_Y0_3") (class "Default")
      (node (ref "U35") (pin "3") (pinfunction "CN_3") (pintype "power_in"))
    )
    (net (code "24") (name "/VINP_Y1") (class "Default")
      (node (ref "P14") (pin "1") (pinfunction "X_1") (pintype "passive"))
      (node (ref "U8") (pin "3") (pinfunction "CN_3") (pintype "power_in"))
    )
    (net (code "25") (name "/VN_X0") (class "Default")
      (node (ref "P15") (pin "1") (pinfunction "X_1") (pintype "passive"))
      (node (ref "R13") (pin "2") (pinfunction "2_2") (pintype "passive"))
      (node (ref "U14") (pin "2") (pinfunction "CP_2") (pintype "power_in"))
    )
    (net (code "26") (name "/VN_X0_2") (class "Default")
      (node (ref "R9") (pin "2") (pinfunction "2_2") (pintype "passive"))
      (node (ref "U7") (pin "2") (pinfunction "CP_2") (pintype "power_in"))
    )
    (net (code "27") (name "/VN_X0_3") (class "Default")
      (node (ref "R19") (pin "2") (pinfunction "2_2") (pintype "passive"))
      (node (ref "U27") (pin "2") (pinfunction "CP_2") (pintype "power_in"))
    )
    (net (code "28") (name "/VN_X1") (class "Default")
      (node (ref "P16") (pin "1") (pinfunction "X_1") (pintype "passive"))
      (node (ref "R14") (pin "2") (pinfunction "2_2") (pintype "passive"))
      (node (ref "U15") (pin "2") (pinfunction "CP_2") (pintype "power_in"))
    )
    (net (code "29") (name "/VN_Y0") (class "Default")
      (node (ref "P23") (pin "1") (pinfunction "X_1") (pintype "passive"))
      (node (ref "R20") (pin "2") (pinfunction "2_2") (pintype "passive"))
      (node (ref "U28") (pin "2") (pinfunction "CP_2") (pintype "power_in"))
    )
    (net (code "30") (name "/VN_Y0_1") (class "Default")
      (node (ref "R8") (pin "2") (pinfunction "2_2") (pintype "passive"))
      (node (ref "U3") (pin "2") (pinfunction "CP_2") (pintype "power_in"))
    )
    (net (code "31") (name "/VN_Y0_2") (class "Default")
      (node (ref "R12") (pin "2") (pinfunction "2_2") (pintype "passive"))
      (node (ref "U13") (pin "2") (pinfunction "CP_2") (pintype "power_in"))
    )
    (net (code "32") (name "/VN_Y0_3") (class "Default")
      (node (ref "R21") (pin "2") (pinfunction "2_2") (pintype "passive"))
      (node (ref "U31") (pin "2") (pinfunction "CP_2") (pintype "power_in"))
    )
    (net (code "33") (name "/VN_Y1") (class "Default")
      (node (ref "P10") (pin "1") (pinfunction "X_1") (pintype "passive"))
      (node (ref "R7") (pin "2") (pinfunction "2_2") (pintype "passive"))
      (node (ref "U2") (pin "2") (pinfunction "CP_2") (pintype "power_in"))
    )
    (net (code "34") (name "/VP_X0") (class "Default")
      (node (ref "P19") (pin "1") (pinfunction "X_1") (pintype "passive"))
      (node (ref "R16") (pin "2") (pinfunction "2_2") (pintype "passive"))
      (node (ref "U20") (pin "2") (pinfunction "CP_2") (pintype "power_in"))
    )
    (net (code "35") (name "/VP_X0_2") (class "Default")
      (node (ref "R6") (pin "2") (pinfunction "2_2") (pintype "passive"))
      (node (ref "U1") (pin "2") (pinfunction "CP_2") (pintype "power_in"))
    )
    (net (code "36") (name "/VP_X0_3") (class "Default")
      (node (ref "R17") (pin "2") (pinfunction "2_2") (pintype "passive"))
      (node (ref "U21") (pin "2") (pinfunction "CP_2") (pintype "power_in"))
    )
    (net (code "37") (name "/VP_X1") (class "Default")
      (node (ref "P20") (pin "1") (pinfunction "X_1") (pintype "passive"))
      (node (ref "R18") (pin "2") (pinfunction "2_2") (pintype "passive"))
      (node (ref "U22") (pin "2") (pinfunction "CP_2") (pintype "power_in"))
    )
    (net (code "38") (name "/VP_Y0") (class "Default")
      (node (ref "P25") (pin "1") (pinfunction "X_1") (pintype "passive"))
      (node (ref "R22") (pin "2") (pinfunction "2_2") (pintype "passive"))
      (node (ref "U32") (pin "2") (pinfunction "CP_2") (pintype "power_in"))
    )
    (net (code "39") (name "/VP_Y0_1") (class "Default")
      (node (ref "R11") (pin "2") (pinfunction "2_2") (pintype "passive"))
      (node (ref "U9") (pin "2") (pinfunction "CP_2") (pintype "power_in"))
    )
    (net (code "40") (name "/VP_Y0_2") (class "Default")
      (node (ref "R15") (pin "2") (pinfunction "2_2") (pintype "passive"))
      (node (ref "U18") (pin "2") (pinfunction "CP_2") (pintype "power_in"))
    )
    (net (code "41") (name "/VP_Y0_3") (class "Default")
      (node (ref "R23") (pin "2") (pinfunction "2_2") (pintype "passive"))
      (node (ref "U35") (pin "2") (pinfunction "CP_2") (pintype "power_in"))
    )
    (net (code "42") (name "/VP_Y1") (class "Default")
      (node (ref "P13") (pin "1") (pinfunction "X_1") (pintype "passive"))
      (node (ref "R10") (pin "2") (pinfunction "2_2") (pintype "passive"))
      (node (ref "U8") (pin "2") (pinfunction "CP_2") (pintype "power_in"))
    )
    (net (code "43") (name "/X0_CSN_SCL") (class "Default")
      (node (ref "U14") (pin "6") (pinfunction "SCL_6") (pintype "input"))
      (node (ref "U27") (pin "6") (pinfunction "SCL_6") (pintype "input"))
      (node (ref "U7") (pin "6") (pinfunction "SCL_6") (pintype "input"))
    )
    (net (code "44") (name "/X0_CSN_SDA") (class "Default")
      (node (ref "U14") (pin "1") (pinfunction "SDA_1") (pintype "bidirectional"))
      (node (ref "U27") (pin "1") (pinfunction "SDA_1") (pintype "bidirectional"))
      (node (ref "U7") (pin "1") (pinfunction "SDA_1") (pintype "bidirectional"))
    )
    (net (code "45") (name "/X0_CSP_SCL") (class "Default")
      (node (ref "U1") (pin "6") (pinfunction "SCL_6") (pintype "input"))
      (node (ref "U20") (pin "6") (pinfunction "SCL_6") (pintype "input"))
      (node (ref "U21") (pin "6") (pinfunction "SCL_6") (pintype "input"))
    )
    (net (code "46") (name "/X0_CSP_SDA") (class "Default")
      (node (ref "U1") (pin "1") (pinfunction "SDA_1") (pintype "bidirectional"))
      (node (ref "U20") (pin "1") (pinfunction "SDA_1") (pintype "bidirectional"))
      (node (ref "U21") (pin "1") (pinfunction "SDA_1") (pintype "bidirectional"))
    )
    (net (code "47") (name "/X1_CSN_SCL") (class "Default")
      (node (ref "U15") (pin "6") (pinfunction "SCL_6") (pintype "input"))
    )
    (net (code "48") (name "/X1_CSN_SDA") (class "Default")
      (node (ref "U15") (pin "1") (pinfunction "SDA_1") (pintype "bidirectional"))
    )
    (net (code "49") (name "/X1_CSP_SCL") (class "Default")
      (node (ref "U22") (pin "6") (pinfunction "SCL_6") (pintype "input"))
    )
    (net (code "50") (name "/X1_CSP_SDA") (class "Default")
      (node (ref "U22") (pin "1") (pinfunction "SDA_1") (pintype "bidirectional"))
    )
    (net (code "51") (name "/Y0_CSN_SCL") (class "Default")
      (node (ref "U13") (pin "6") (pinfunction "SCL_6") (pintype "input"))
      (node (ref "U28") (pin "6") (pinfunction "SCL_6") (pintype "input"))
      (node (ref "U3") (pin "6") (pinfunction "SCL_6") (pintype "input"))
      (node (ref "U31") (pin "6") (pinfunction "SCL_6") (pintype "input"))
    )
    (net (code "52") (name "/Y0_CSN_SDA") (class "Default")
      (node (ref "U13") (pin "1") (pinfunction "SDA_1") (pintype "bidirectional"))
      (node (ref "U28") (pin "1") (pinfunction "SDA_1") (pintype "bidirectional"))
      (node (ref "U3") (pin "1") (pinfunction "SDA_1") (pintype "bidirectional"))
      (node (ref "U31") (pin "1") (pinfunction "SDA_1") (pintype "bidirectional"))
    )
    (net (code "53") (name "/Y0_CSP_SCL") (class "Default")
      (node (ref "U18") (pin "6") (pinfunction "SCL_6") (pintype "input"))
      (node (ref "U32") (pin "6") (pinfunction "SCL_6") (pintype "input"))
      (node (ref "U35") (pin "6") (pinfunction "SCL_6") (pintype "input"))
      (node (ref "U9") (pin "6") (pinfunction "SCL_6") (pintype "input"))
    )
    (net (code "54") (name "/Y0_CSP_SDA") (class "Default")
      (node (ref "U18") (pin "1") (pinfunction "SDA_1") (pintype "bidirectional"))
      (node (ref "U32") (pin "1") (pinfunction "SDA_1") (pintype "bidirectional"))
      (node (ref "U35") (pin "1") (pinfunction "SDA_1") (pintype "bidirectional"))
      (node (ref "U9") (pin "1") (pinfunction "SDA_1") (pintype "bidirectional"))
    )
    (net (code "55") (name "/Y1_CSN_SCL") (class "Default")
      (node (ref "U2") (pin "6") (pinfunction "SCL_6") (pintype "input"))
    )
    (net (code "56") (name "/Y1_CSN_SDA") (class "Default")
      (node (ref "U2") (pin "1") (pinfunction "SDA_1") (pintype "bidirectional"))
    )
    (net (code "57") (name "/Y1_CSP_SCL") (class "Default")
      (node (ref "U8") (pin "6") (pinfunction "SCL_6") (pintype "input"))
    )
    (net (code "58") (name "/Y1_CSP_SDA") (class "Default")
      (node (ref "U8") (pin "1") (pinfunction "SDA_1") (pintype "bidirectional"))
    )
    (net (code "59") (name "AGND") (class "Default")
      (node (ref "P12") (pin "3") (pinfunction "3_3") (pintype "passive"))
    )
    (net (code "60") (name "GND") (class "Default")
      (node (ref "C1") (pin "2") (pintype "passive"))
      (node (ref "C10") (pin "2") (pintype "passive"))
      (node (ref "C11") (pin "2") (pintype "passive"))
      (node (ref "C12") (pin "2") (pintype "passive"))
      (node (ref "C13") (pin "2") (pintype "passive"))
      (node (ref "C14") (pin "2") (pintype "passive"))
      (node (ref "C15") (pin "2") (pintype "passive"))
      (node (ref "C16") (pin "2") (pintype "passive"))
      (node (ref "C17") (pin "2") (pintype "passive"))
      (node (ref "C18") (pin "2") (pintype "passive"))
      (node (ref "C19") (pin "2") (pintype "passive"))
      (node (ref "C2") (pin "2") (pintype "passive"))
      (node (ref "C20") (pin "2") (pintype "passive"))
      (node (ref "C21") (pin "2") (pintype "passive"))
      (node (ref "C22") (pin "2") (pintype "passive"))
      (node (ref "C23") (pin "2") (pintype "passive"))
      (node (ref "C24") (pin "2") (pintype "passive"))
      (node (ref "C25") (pin "2") (pintype "passive"))
      (node (ref "C26") (pin "2") (pintype "passive"))
      (node (ref "C27") (pin "2") (pintype "passive"))
      (node (ref "C28") (pin "2") (pintype "passive"))
      (node (ref "C29") (pin "2") (pintype "passive"))
      (node (ref "C3") (pin "2") (pintype "passive"))
      (node (ref "C30") (pin "2") (pintype "passive"))
      (node (ref "C31") (pin "2") (pintype "passive"))
      (node (ref "C32") (pin "2") (pintype "passive"))
      (node (ref "C33") (pin "2") (pintype "passive"))
      (node (ref "C34") (pin "2") (pintype "passive"))
      (node (ref "C35") (pin "2") (pintype "passive"))
      (node (ref "C36") (pin "2") (pintype "passive"))
      (node (ref "C4") (pin "2") (pintype "passive"))
      (node (ref "C5") (pin "2") (pintype "passive"))
      (node (ref "C6") (pin "2") (pintype "passive"))
      (node (ref "C7") (pin "2") (pintype "passive"))
      (node (ref "C8") (pin "2") (pintype "passive"))
      (node (ref "C9") (pin "2") (pintype "passive"))
      (node (ref "U1") (pin "5") (pinfunction "GND_5") (pintype "power_in"))
      (node (ref "U1") (pin "7") (pinfunction "GND_7") (pintype "power_in"))
      (node (ref "U10") (pin "5") (pinfunction "GND_5") (pintype "power_in"))
      (node (ref "U10") (pin "7") (pinfunction "GND_7") (pintype "power_in"))
      (node (ref "U11") (pin "5") (pinfunction "GND_5") (pintype "power_in"))
      (node (ref "U11") (pin "7") (pinfunction "GND_7") (pintype "power_in"))
      (node (ref "U12") (pin "5") (pinfunction "GND_5") (pintype "power_in"))
      (node (ref "U12") (pin "7") (pinfunction "GND_7") (pintype "power_in"))
      (node (ref "U13") (pin "5") (pinfunction "GND_5") (pintype "power_in"))
      (node (ref "U13") (pin "7") (pinfunction "GND_7") (pintype "power_in"))
      (node (ref "U14") (pin "5") (pinfunction "GND_5") (pintype "power_in"))
      (node (ref "U14") (pin "7") (pinfunction "GND_7") (pintype "power_in"))
      (node (ref "U15") (pin "5") (pinfunction "GND_5") (pintype "power_in"))
      (node (ref "U15") (pin "7") (pinfunction "GND_7") (pintype "power_in"))
      (node (ref "U16") (pin "5") (pinfunction "GND_5") (pintype "power_in"))
      (node (ref "U16") (pin "7") (pinfunction "GND_7") (pintype "power_in"))
      (node (ref "U17") (pin "5") (pinfunction "GND_5") (pintype "power_in"))
      (node (ref "U17") (pin "7") (pinfunction "GND_7") (pintype "power_in"))
      (node (ref "U18") (pin "5") (pinfunction "GND_5") (pintype "power_in"))
      (node (ref "U18") (pin "7") (pinfunction "GND_7") (pintype "power_in"))
      (node (ref "U19") (pin "5") (pinfunction "GND_5") (pintype "power_in"))
      (node (ref "U19") (pin "7") (pinfunction "GND_7") (pintype "power_in"))
      (node (ref "U2") (pin "5") (pinfunction "GND_5") (pintype "power_in"))
      (node (ref "U2") (pin "7") (pinfunction "GND_7") (pintype "power_in"))
      (node (ref "U20") (pin "5") (pinfunction "GND_5") (pintype "power_in"))
      (node (ref "U20") (pin "7") (pinfunction "GND_7") (pintype "power_in"))
      (node (ref "U21") (pin "5") (pinfunction "GND_5") (pintype "power_in"))
      (node (ref "U21") (pin "7") (pinfunction "GND_7") (pintype "power_in"))
      (node (ref "U22") (pin "5") (pinfunction "GND_5") (pintype "power_in"))
      (node (ref "U22") (pin "7") (pinfunction "GND_7") (pintype "power_in"))
      (node (ref "U23") (pin "5") (pinfunction "GND_5") (pintype "power_in"))
      (node (ref "U23") (pin "7") (pinfunction "GND_7") (pintype "power_in"))
      (node (ref "U24") (pin "5") (pinfunction "GND_5") (pintype "power_in"))
      (node (ref "U24") (pin "7") (pinfunction "GND_7") (pintype "power_in"))
      (node (ref "U25") (pin "5") (pinfunction "GND_5") (pintype "power_in"))
      (node (ref "U25") (pin "7") (pinfunction "GND_7") (pintype "power_in"))
      (node (ref "U26") (pin "5") (pinfunction "GND_5") (pintype "power_in"))
      (node (ref "U26") (pin "7") (pinfunction "GND_7") (pintype "power_in"))
      (node (ref "U27") (pin "5") (pinfunction "GND_5") (pintype "power_in"))
      (node (ref "U27") (pin "7") (pinfunction "GND_7") (pintype "power_in"))
      (node (ref "U28") (pin "5") (pinfunction "GND_5") (pintype "power_in"))
      (node (ref "U28") (pin "7") (pinfunction "GND_7") (pintype "power_in"))
      (node (ref "U29") (pin "5") (pinfunction "GND_5") (pintype "power_in"))
      (node (ref "U29") (pin "7") (pinfunction "GND_7") (pintype "power_in"))
      (node (ref "U3") (pin "5") (pinfunction "GND_5") (pintype "power_in"))
      (node (ref "U3") (pin "7") (pinfunction "GND_7") (pintype "power_in"))
      (node (ref "U30") (pin "5") (pinfunction "GND_5") (pintype "power_in"))
      (node (ref "U30") (pin "7") (pinfunction "GND_7") (pintype "power_in"))
      (node (ref "U31") (pin "5") (pinfunction "GND_5") (pintype "power_in"))
      (node (ref "U31") (pin "7") (pinfunction "GND_7") (pintype "power_in"))
      (node (ref "U32") (pin "5") (pinfunction "GND_5") (pintype "power_in"))
      (node (ref "U32") (pin "7") (pinfunction "GND_7") (pintype "power_in"))
      (node (ref "U33") (pin "5") (pinfunction "GND_5") (pintype "power_in"))
      (node (ref "U33") (pin "7") (pinfunction "GND_7") (pintype "power_in"))
      (node (ref "U34") (pin "5") (pinfunction "GND_5") (pintype "power_in"))
      (node (ref "U34") (pin "7") (pinfunction "GND_7") (pintype "power_in"))
      (node (ref "U35") (pin "5") (pinfunction "GND_5") (pintype "power_in"))
      (node (ref "U35") (pin "7") (pinfunction "GND_7") (pintype "power_in"))
      (node (ref "U36") (pin "5") (pinfunction "GND_5") (pintype "power_in"))
      (node (ref "U36") (pin "7") (pinfunction "GND_7") (pintype "power_in"))
      (node (ref "U4") (pin "5") (pinfunction "GND_5") (pintype "power_in"))
      (node (ref "U4") (pin "7") (pinfunction "GND_7") (pintype "power_in"))
      (node (ref "U5") (pin "5") (pinfunction "GND_5") (pintype "power_in"))
      (node (ref "U5") (pin "7") (pinfunction "GND_7") (pintype "power_in"))
      (node (ref "U6") (pin "5") (pinfunction "GND_5") (pintype "power_in"))
      (node (ref "U6") (pin "7") (pinfunction "GND_7") (pintype "power_in"))
      (node (ref "U7") (pin "5") (pinfunction "GND_5") (pintype "power_in"))
      (node (ref "U7") (pin "7") (pinfunction "GND_7") (pintype "power_in"))
      (node (ref "U8") (pin "5") (pinfunction "GND_5") (pintype "power_in"))
      (node (ref "U8") (pin "7") (pinfunction "GND_7") (pintype "power_in"))
      (node (ref "U9") (pin "5") (pinfunction "GND_5") (pintype "power_in"))
      (node (ref "U9") (pin "7") (pinfunction "GND_7") (pintype "power_in"))
    )
    (net (code "61") (name "Net-(U4-CP)") (class "Default")
      (node (ref "R6") (pin "1") (pinfunction "1_1") (pintype "passive"))
      (node (ref "U4") (pin "2") (pinfunction "CP_2") (pintype "power_in"))
    )
    (net (code "62") (name "Net-(U5-CP)") (class "Default")
      (node (ref "R7") (pin "1") (pinfunction "1_1") (pintype "passive"))
      (node (ref "U5") (pin "2") (pinfunction "CP_2") (pintype "power_in"))
    )
    (net (code "63") (name "Net-(U6-CP)") (class "Default")
      (node (ref "R8") (pin "1") (pinfunction "1_1") (pintype "passive"))
      (node (ref "U6") (pin "2") (pinfunction "CP_2") (pintype "power_in"))
    )
    (net (code "64") (name "Net-(U10-CP)") (class "Default")
      (node (ref "R9") (pin "1") (pinfunction "1_1") (pintype "passive"))
      (node (ref "U10") (pin "2") (pinfunction "CP_2") (pintype "power_in"))
    )
    (net (code "65") (name "Net-(U11-CP)") (class "Default")
      (node (ref "R10") (pin "1") (pinfunction "1_1") (pintype "passive"))
      (node (ref "U11") (pin "2") (pinfunction "CP_2") (pintype "power_in"))
    )
    (net (code "66") (name "Net-(U12-CP)") (class "Default")
      (node (ref "R11") (pin "1") (pinfunction "1_1") (pintype "passive"))
      (node (ref "U12") (pin "2") (pinfunction "CP_2") (pintype "power_in"))
    )
    (net (code "67") (name "Net-(U16-CP)") (class "Default")
      (node (ref "R12") (pin "1") (pinfunction "1_1") (pintype "passive"))
      (node (ref "U16") (pin "2") (pinfunction "CP_2") (pintype "power_in"))
    )
    (net (code "68") (name "Net-(U17-CP)") (class "Default")
      (node (ref "R13") (pin "1") (pinfunction "1_1") (pintype "passive"))
      (node (ref "U17") (pin "2") (pinfunction "CP_2") (pintype "power_in"))
    )
    (net (code "69") (name "Net-(U19-CP)") (class "Default")
      (node (ref "R14") (pin "1") (pinfunction "1_1") (pintype "passive"))
      (node (ref "U19") (pin "2") (pinfunction "CP_2") (pintype "power_in"))
    )
    (net (code "70") (name "Net-(U23-CP)") (class "Default")
      (node (ref "R15") (pin "1") (pinfunction "1_1") (pintype "passive"))
      (node (ref "U23") (pin "2") (pinfunction "CP_2") (pintype "power_in"))
    )
    (net (code "71") (name "Net-(U24-CP)") (class "Default")
      (node (ref "R16") (pin "1") (pinfunction "1_1") (pintype "passive"))
      (node (ref "U24") (pin "2") (pinfunction "CP_2") (pintype "power_in"))
    )
    (net (code "72") (name "Net-(U25-CP)") (class "Default")
      (node (ref "R17") (pin "1") (pinfunction "1_1") (pintype "passive"))
      (node (ref "U25") (pin "2") (pinfunction "CP_2") (pintype "power_in"))
    )
    (net (code "73") (name "Net-(U26-CP)") (class "Default")
      (node (ref "R18") (pin "1") (pinfunction "1_1") (pintype "passive"))
      (node (ref "U26") (pin "2") (pinfunction "CP_2") (pintype "power_in"))
    )
    (net (code "74") (name "Net-(U29-CP)") (class "Default")
      (node (ref "R19") (pin "1") (pinfunction "1_1") (pintype "passive"))
      (node (ref "U29") (pin "2") (pinfunction "CP_2") (pintype "power_in"))
    )
    (net (code "75") (name "Net-(U30-CP)") (class "Default")
      (node (ref "R20") (pin "1") (pinfunction "1_1") (pintype "passive"))
      (node (ref "U30") (pin "2") (pinfunction "CP_2") (pintype "power_in"))
    )
    (net (code "76") (name "Net-(U33-CP)") (class "Default")
      (node (ref "R21") (pin "1") (pinfunction "1_1") (pintype "passive"))
      (node (ref "U33") (pin "2") (pinfunction "CP_2") (pintype "power_in"))
    )
    (net (code "77") (name "Net-(U34-CP)") (class "Default")
      (node (ref "R22") (pin "1") (pinfunction "1_1") (pintype "passive"))
      (node (ref "U34") (pin "2") (pinfunction "CP_2") (pintype "power_in"))
    )
    (net (code "78") (name "Net-(U36-CP)") (class "Default")
      (node (ref "R23") (pin "1") (pinfunction "1_1") (pintype "passive"))
      (node (ref "U36") (pin "2") (pinfunction "CP_2") (pintype "power_in"))
    )
    (net (code "79") (name "VDD_3P3V_IN") (class "Default")
      (node (ref "C1") (pin "1") (pintype "passive"))
      (node (ref "C10") (pin "1") (pintype "passive"))
      (node (ref "C11") (pin "1") (pintype "passive"))
      (node (ref "C12") (pin "1") (pintype "passive"))
      (node (ref "C13") (pin "1") (pintype "passive"))
      (node (ref "C14") (pin "1") (pintype "passive"))
      (node (ref "C15") (pin "1") (pintype "passive"))
      (node (ref "C16") (pin "1") (pintype "passive"))
      (node (ref "C17") (pin "1") (pintype "passive"))
      (node (ref "C18") (pin "1") (pintype "passive"))
      (node (ref "C19") (pin "1") (pintype "passive"))
      (node (ref "C2") (pin "1") (pintype "passive"))
      (node (ref "C20") (pin "1") (pintype "passive"))
      (node (ref "C21") (pin "1") (pintype "passive"))
      (node (ref "C22") (pin "1") (pintype "passive"))
      (node (ref "C23") (pin "1") (pintype "passive"))
      (node (ref "C24") (pin "1") (pintype "passive"))
      (node (ref "C25") (pin "1") (pintype "passive"))
      (node (ref "C26") (pin "1") (pintype "passive"))
      (node (ref "C27") (pin "1") (pintype "passive"))
      (node (ref "C28") (pin "1") (pintype "passive"))
      (node (ref "C29") (pin "1") (pintype "passive"))
      (node (ref "C3") (pin "1") (pintype "passive"))
      (node (ref "C30") (pin "1") (pintype "passive"))
      (node (ref "C31") (pin "1") (pintype "passive"))
      (node (ref "C32") (pin "1") (pintype "passive"))
      (node (ref "C33") (pin "1") (pintype "passive"))
      (node (ref "C34") (pin "1") (pintype "passive"))
      (node (ref "C35") (pin "1") (pintype "passive"))
      (node (ref "C36") (pin "1") (pintype "passive"))
      (node (ref "C4") (pin "1") (pintype "passive"))
      (node (ref "C5") (pin "1") (pintype "passive"))
      (node (ref "C6") (pin "1") (pintype "passive"))
      (node (ref "C7") (pin "1") (pintype "passive"))
      (node (ref "C8") (pin "1") (pintype "passive"))
      (node (ref "C9") (pin "1") (pintype "passive"))
      (node (ref "U1") (pin "4") (pinfunction "VDD_4") (pintype "power_in"))
      (node (ref "U10") (pin "4") (pinfunction "VDD_4") (pintype "power_in"))
      (node (ref "U11") (pin "4") (pinfunction "VDD_4") (pintype "power_in"))
      (node (ref "U12") (pin "4") (pinfunction "VDD_4") (pintype "power_in"))
      (node (ref "U13") (pin "4") (pinfunction "VDD_4") (pintype "power_in"))
      (node (ref "U14") (pin "4") (pinfunction "VDD_4") (pintype "power_in"))
      (node (ref "U15") (pin "4") (pinfunction "VDD_4") (pintype "power_in"))
      (node (ref "U16") (pin "4") (pinfunction "VDD_4") (pintype "power_in"))
      (node (ref "U17") (pin "4") (pinfunction "VDD_4") (pintype "power_in"))
      (node (ref "U18") (pin "4") (pinfunction "VDD_4") (pintype "power_in"))
      (node (ref "U19") (pin "4") (pinfunction "VDD_4") (pintype "power_in"))
      (node (ref "U2") (pin "4") (pinfunction "VDD_4") (pintype "power_in"))
      (node (ref "U20") (pin "4") (pinfunction "VDD_4") (pintype "power_in"))
      (node (ref "U21") (pin "4") (pinfunction "VDD_4") (pintype "power_in"))
      (node (ref "U22") (pin "4") (pinfunction "VDD_4") (pintype "power_in"))
      (node (ref "U23") (pin "4") (pinfunction "VDD_4") (pintype "power_in"))
      (node (ref "U24") (pin "4") (pinfunction "VDD_4") (pintype "power_in"))
      (node (ref "U25") (pin "4") (pinfunction "VDD_4") (pintype "power_in"))
      (node (ref "U26") (pin "4") (pinfunction "VDD_4") (pintype "power_in"))
      (node (ref "U27") (pin "4") (pinfunction "VDD_4") (pintype "power_in"))
      (node (ref "U28") (pin "4") (pinfunction "VDD_4") (pintype "power_in"))
      (node (ref "U29") (pin "4") (pinfunction "VDD_4") (pintype "power_in"))
      (node (ref "U3") (pin "4") (pinfunction "VDD_4") (pintype "power_in"))
      (node (ref "U30") (pin "4") (pinfunction "VDD_4") (pintype "power_in"))
      (node (ref "U31") (pin "4") (pinfunction "VDD_4") (pintype "power_in"))
      (node (ref "U32") (pin "4") (pinfunction "VDD_4") (pintype "power_in"))
      (node (ref "U33") (pin "4") (pinfunction "VDD_4") (pintype "power_in"))
      (node (ref "U34") (pin "4") (pinfunction "VDD_4") (pintype "power_in"))
      (node (ref "U35") (pin "4") (pinfunction "VDD_4") (pintype "power_in"))
      (node (ref "U36") (pin "4") (pinfunction "VDD_4") (pintype "power_in"))
      (node (ref "U4") (pin "4") (pinfunction "VDD_4") (pintype "power_in"))
      (node (ref "U5") (pin "4") (pinfunction "VDD_4") (pintype "power_in"))
      (node (ref "U6") (pin "4") (pinfunction "VDD_4") (pintype "power_in"))
      (node (ref "U7") (pin "4") (pinfunction "VDD_4") (pintype "power_in"))
      (node (ref "U8") (pin "4") (pinfunction "VDD_4") (pintype "power_in"))
      (node (ref "U9") (pin "4") (pinfunction "VDD_4") (pintype "power_in"))
    )
  )
)
